# Sheet.net
KiCad netlist of a schematic drawn in Altium Designer
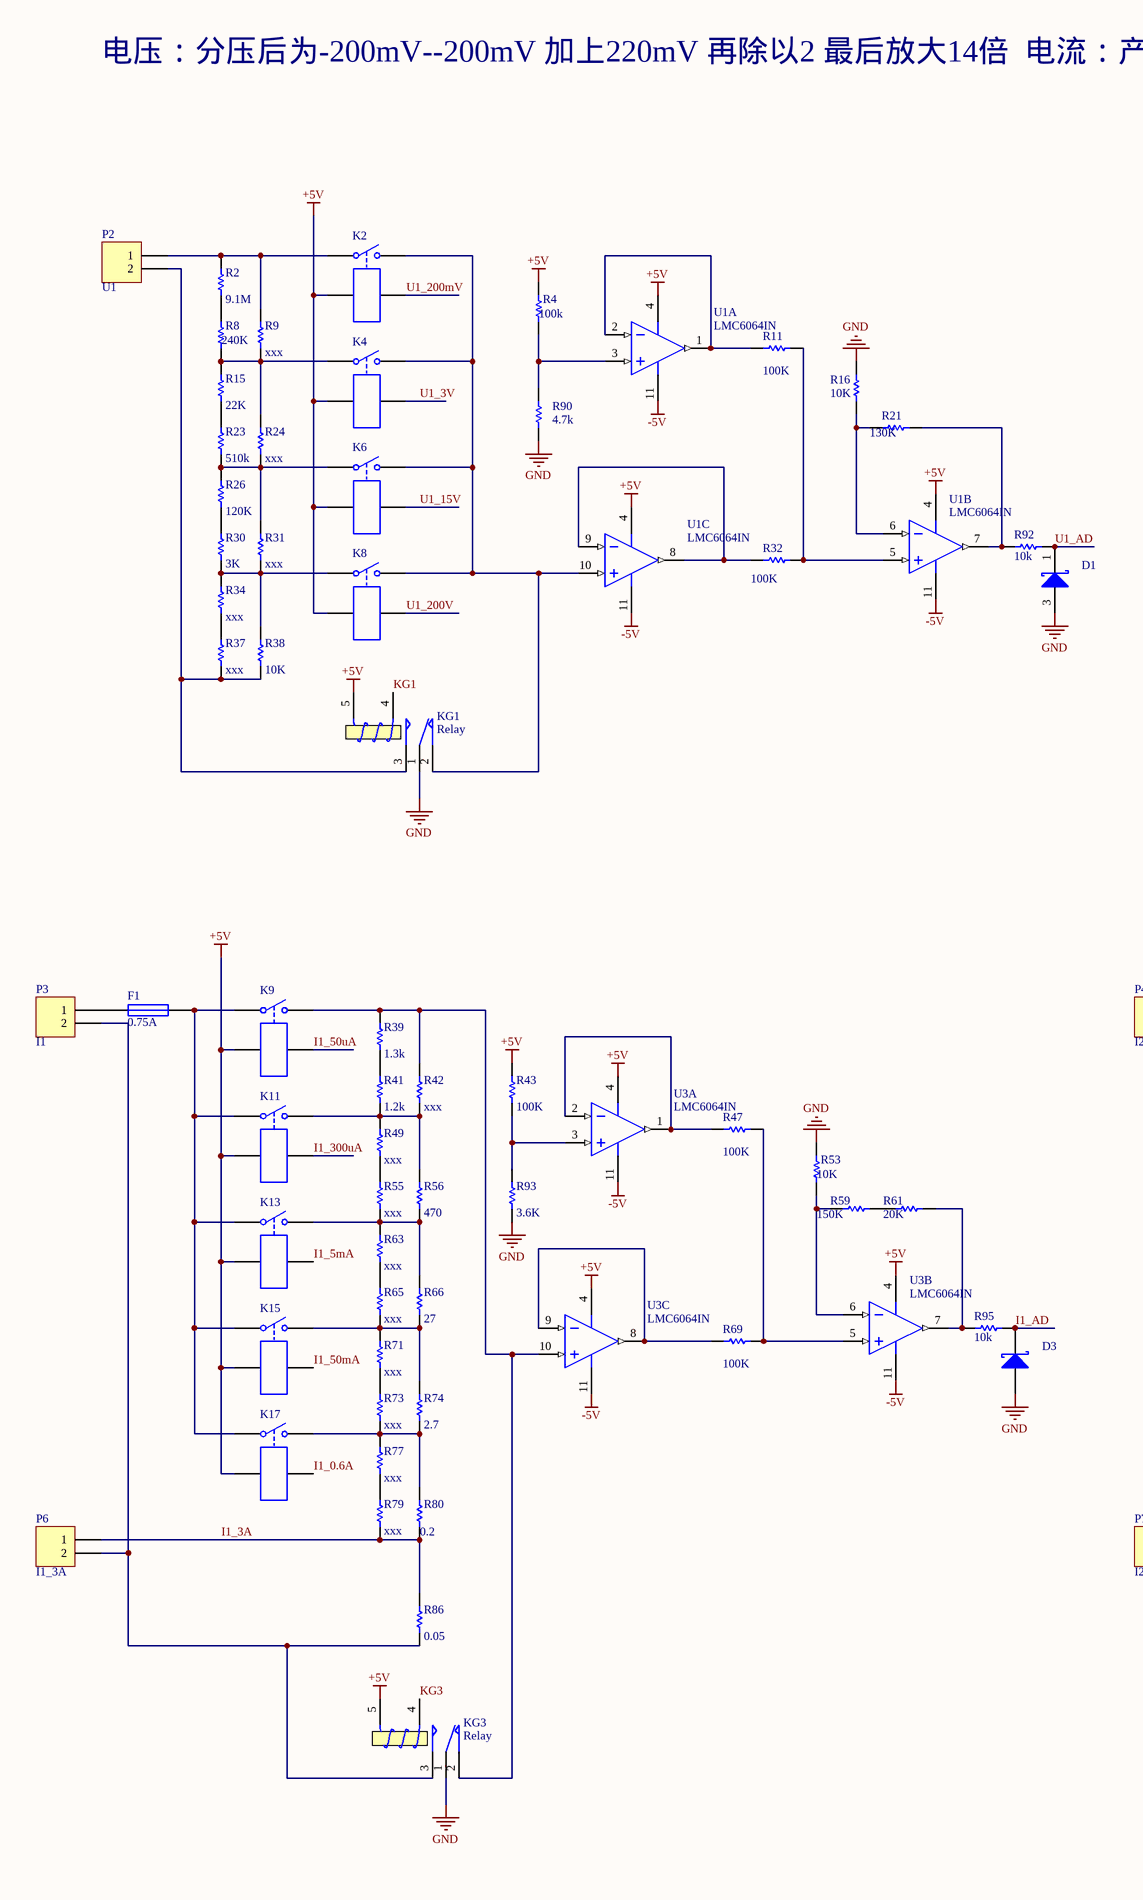
[diagram p0: Sheet.SchDoc, left]
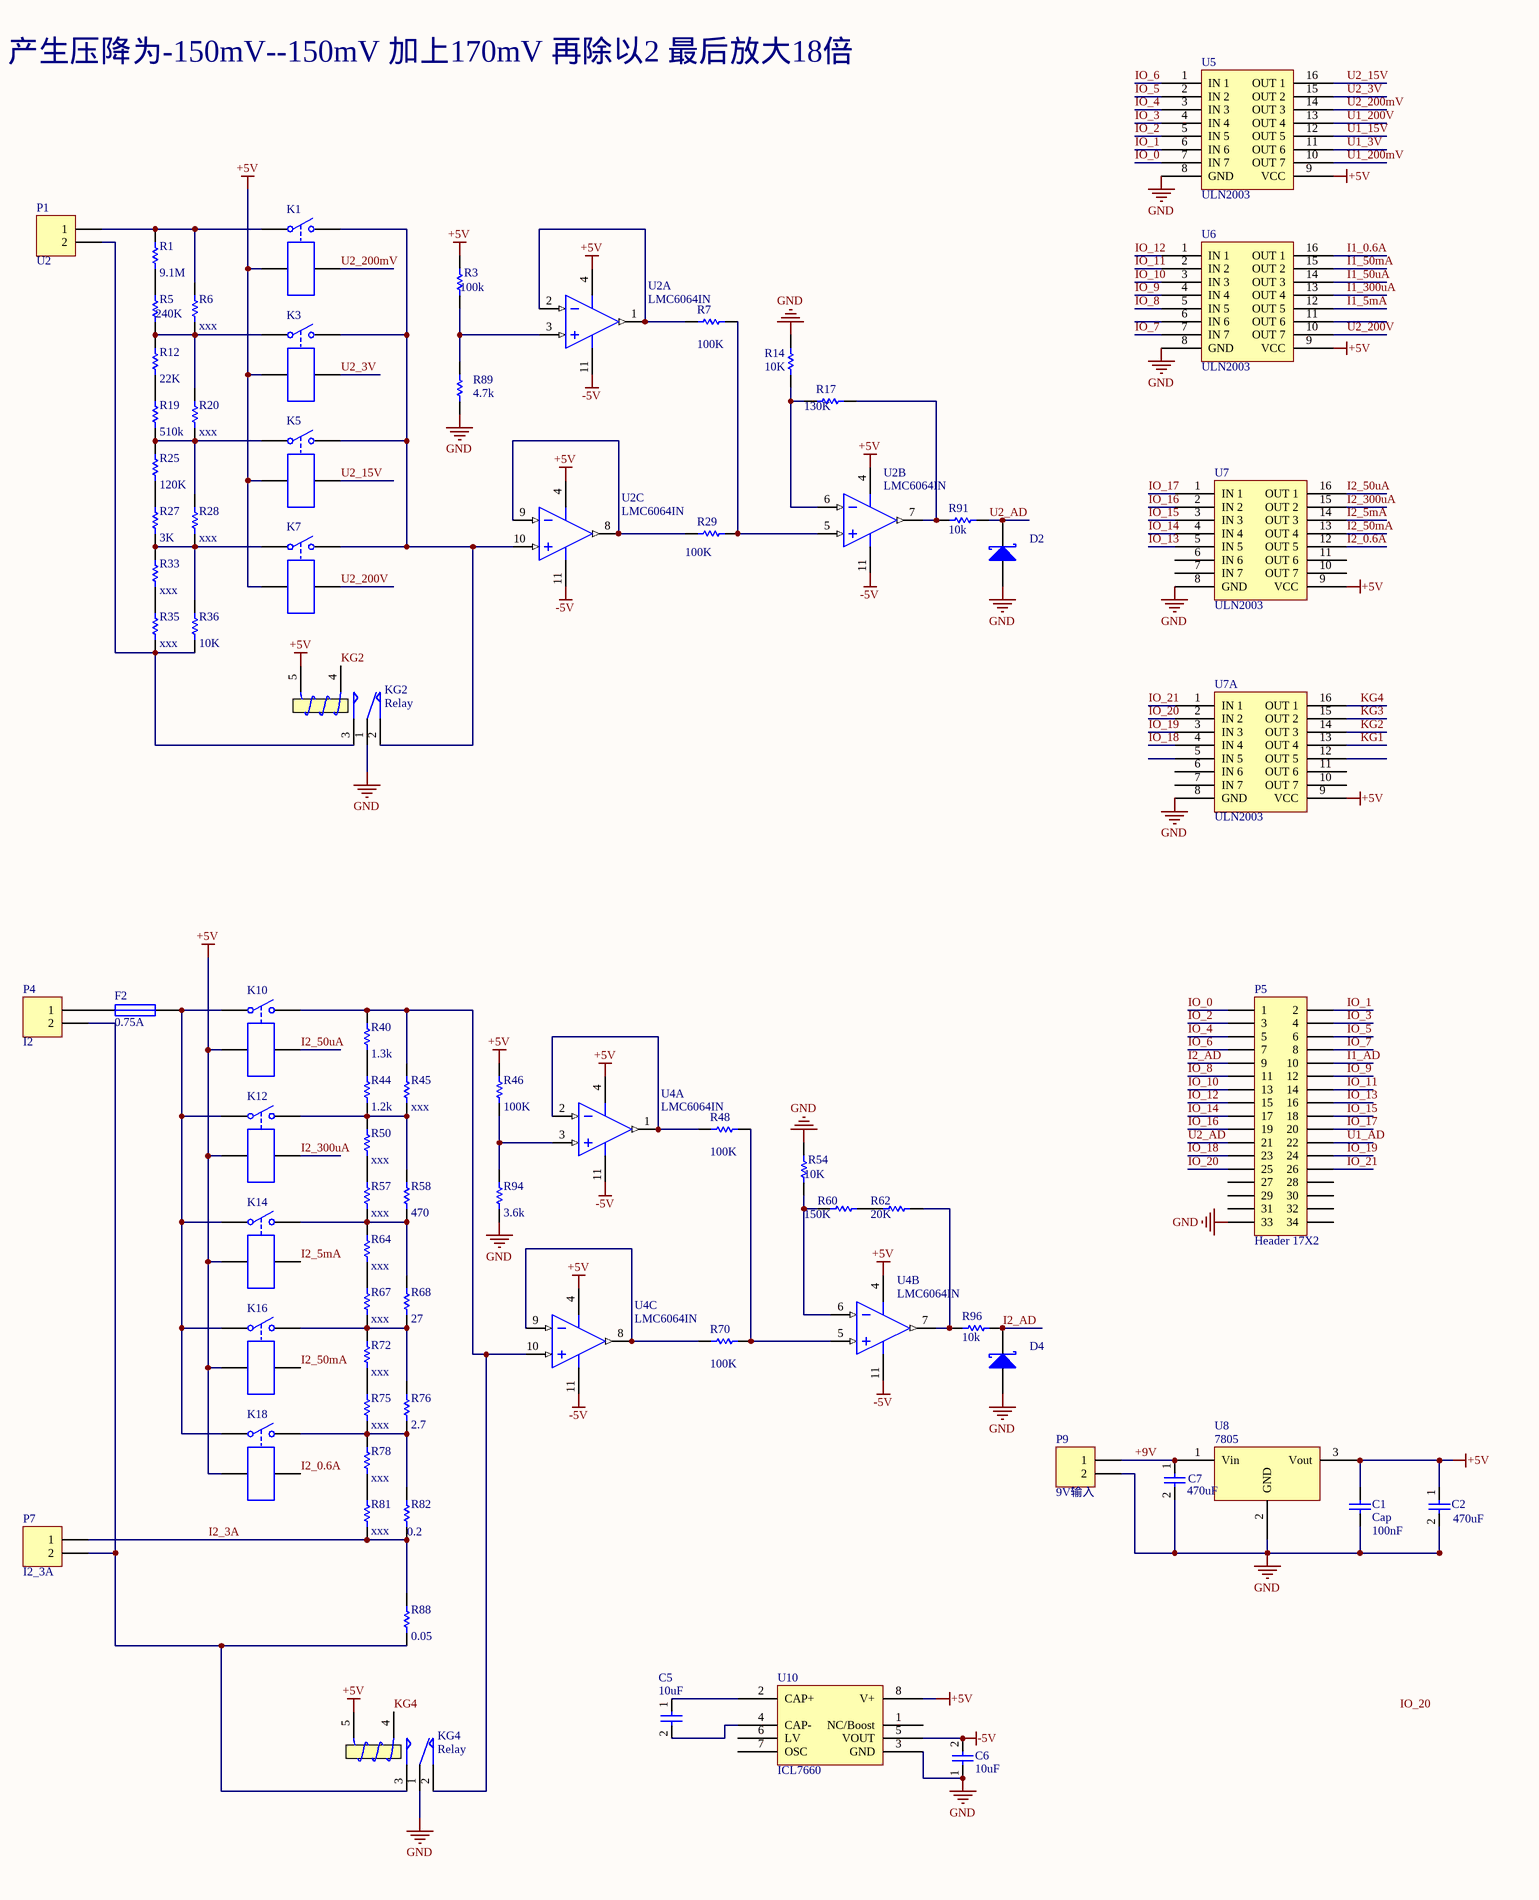
[diagram p1: Sheet.SchDoc, right]

(export (version "E")
  (design (tool "Eeschema 10.0.6"))
  (components
    (comp (ref "C1")
      (value "Cap")
      (footprint "0805")
      (description "Capacitor")
      (fields (field (name "ALTIUM_VALUE") "100nF") (field (name "PUBLISHER") "Altium Limited"))
      (libsource (lib "") (part "Cap_1"))
    )
    (comp (ref "C2")
      (value "470uF")
      (footprint "RB8mm_3.5mm")
      (description "Capacitor")
      (fields (field (name "Comment") "Cap") (field (name "PUBLISHER") "Altium Limited"))
      (libsource (lib "Miscellaneous Devices") (part "Cap"))
    )
    (comp (ref "C5")
      (value "10uF")
      (footprint "RB4.5mm_1.5mm")
      (description "Capacitor")
      (fields (field (name "Comment") "Cap") (field (name "PUBLISHER") "Altium Limited"))
      (libsource (lib "Miscellaneous Devices") (part "Cap"))
    )
    (comp (ref "C6")
      (value "10uF")
      (footprint "RB4.5mm_1.5mm")
      (description "Capacitor")
      (fields (field (name "Comment") "Cap") (field (name "PUBLISHER") "Altium Limited"))
      (libsource (lib "Miscellaneous Devices") (part "Cap"))
    )
    (comp (ref "C7")
      (value "470uF")
      (footprint "RB8mm_3.5mm")
      (description "Capacitor")
      (fields (field (name "Comment") "Cap") (field (name "PUBLISHER") "Altium Limited"))
      (libsource (lib "Miscellaneous Devices") (part "Cap"))
    )
    (comp (ref "D1")
      (value "~")
      (footprint "D1206")
      (description "Schottky Rectifier")
      (fields (field (name "PUBLISHER") "Altium Limited"))
      (libsource (lib "Miscellaneous Devices") (part "Diode 10TQ035"))
    )
    (comp (ref "D2")
      (value "~")
      (footprint "D1206")
      (description "Schottky Rectifier")
      (fields (field (name "PUBLISHER") "Altium Limited"))
      (libsource (lib "") (part "Diode 10TQ035_1"))
    )
    (comp (ref "D3")
      (value "~")
      (footprint "D1206")
      (description "Schottky Rectifier")
      (fields (field (name "PUBLISHER") "Altium Limited"))
      (libsource (lib "") (part "Diode 10TQ035_1"))
    )
    (comp (ref "D4")
      (value "~")
      (footprint "D1206")
      (description "Schottky Rectifier")
      (fields (field (name "PUBLISHER") "Altium Limited"))
      (libsource (lib "") (part "Diode 10TQ035_1"))
    )
    (comp (ref "F1")
      (value "0.75A")
      (footprint "1812")
      (description "Fuse")
      (fields (field (name "PUBLISHER") "Altium Limited"))
      (libsource (lib "Miscellaneous Devices") (part "Fuse 1"))
    )
    (comp (ref "F2")
      (value "0.75A")
      (footprint "1812")
      (description "Fuse")
      (fields (field (name "PUBLISHER") "Altium Limited"))
      (libsource (lib "Miscellaneous Devices") (part "Fuse 1"))
    )
    (comp (ref "K1")
      (value "Relay-SPST")
      (footprint "MyRelay")
      (description "Single-Pole Single-Throw Relay")
      (fields (field (name "PUBLISHER") "Altium Limited"))
      (libsource (lib "Miscellaneous Devices") (part "Relay-SPST"))
    )
    (comp (ref "K2")
      (value "Relay-SPST")
      (footprint "MyRelay")
      (description "Single-Pole Single-Throw Relay")
      (fields (field (name "PUBLISHER") "Altium Limited"))
      (libsource (lib "Miscellaneous Devices") (part "Relay-SPST"))
    )
    (comp (ref "K3")
      (value "Relay-SPST")
      (footprint "MyRelay")
      (description "Single-Pole Single-Throw Relay")
      (fields (field (name "PUBLISHER") "Altium Limited"))
      (libsource (lib "Miscellaneous Devices") (part "Relay-SPST"))
    )
    (comp (ref "K4")
      (value "Relay-SPST")
      (footprint "MyRelay")
      (description "Single-Pole Single-Throw Relay")
      (fields (field (name "PUBLISHER") "Altium Limited"))
      (libsource (lib "Miscellaneous Devices") (part "Relay-SPST"))
    )
    (comp (ref "K5")
      (value "Relay-SPST")
      (footprint "MyRelay")
      (description "Single-Pole Single-Throw Relay")
      (fields (field (name "PUBLISHER") "Altium Limited"))
      (libsource (lib "Miscellaneous Devices") (part "Relay-SPST"))
    )
    (comp (ref "K6")
      (value "Relay-SPST")
      (footprint "MyRelay")
      (description "Single-Pole Single-Throw Relay")
      (fields (field (name "PUBLISHER") "Altium Limited"))
      (libsource (lib "Miscellaneous Devices") (part "Relay-SPST"))
    )
    (comp (ref "K7")
      (value "Relay-SPST")
      (footprint "MyRelay")
      (description "Single-Pole Single-Throw Relay")
      (fields (field (name "PUBLISHER") "Altium Limited"))
      (libsource (lib "Miscellaneous Devices") (part "Relay-SPST"))
    )
    (comp (ref "K8")
      (value "Relay-SPST")
      (footprint "MyRelay")
      (description "Single-Pole Single-Throw Relay")
      (fields (field (name "PUBLISHER") "Altium Limited"))
      (libsource (lib "Miscellaneous Devices") (part "Relay-SPST"))
    )
    (comp (ref "K9")
      (value "Relay-SPST")
      (footprint "MyRelay")
      (description "Single-Pole Single-Throw Relay")
      (fields (field (name "PUBLISHER") "Altium Limited"))
      (libsource (lib "Miscellaneous Devices") (part "Relay-SPST"))
    )
    (comp (ref "K10")
      (value "Relay-SPST")
      (footprint "MyRelay")
      (description "Single-Pole Single-Throw Relay")
      (fields (field (name "PUBLISHER") "Altium Limited"))
      (libsource (lib "Miscellaneous Devices") (part "Relay-SPST"))
    )
    (comp (ref "K11")
      (value "Relay-SPST")
      (footprint "MyRelay")
      (description "Single-Pole Single-Throw Relay")
      (fields (field (name "PUBLISHER") "Altium Limited"))
      (libsource (lib "Miscellaneous Devices") (part "Relay-SPST"))
    )
    (comp (ref "K12")
      (value "Relay-SPST")
      (footprint "MyRelay")
      (description "Single-Pole Single-Throw Relay")
      (fields (field (name "PUBLISHER") "Altium Limited"))
      (libsource (lib "Miscellaneous Devices") (part "Relay-SPST"))
    )
    (comp (ref "K13")
      (value "Relay-SPST")
      (footprint "MyRelay")
      (description "Single-Pole Single-Throw Relay")
      (fields (field (name "PUBLISHER") "Altium Limited"))
      (libsource (lib "Miscellaneous Devices") (part "Relay-SPST"))
    )
    (comp (ref "K14")
      (value "Relay-SPST")
      (footprint "MyRelay")
      (description "Single-Pole Single-Throw Relay")
      (fields (field (name "PUBLISHER") "Altium Limited"))
      (libsource (lib "Miscellaneous Devices") (part "Relay-SPST"))
    )
    (comp (ref "K15")
      (value "Relay-SPST")
      (footprint "MyRelay")
      (description "Single-Pole Single-Throw Relay")
      (fields (field (name "PUBLISHER") "Altium Limited"))
      (libsource (lib "Miscellaneous Devices") (part "Relay-SPST"))
    )
    (comp (ref "K16")
      (value "Relay-SPST")
      (footprint "MyRelay")
      (description "Single-Pole Single-Throw Relay")
      (fields (field (name "PUBLISHER") "Altium Limited"))
      (libsource (lib "Miscellaneous Devices") (part "Relay-SPST"))
    )
    (comp (ref "K17")
      (value "Relay-SPST")
      (footprint "MyRelay")
      (description "Single-Pole Single-Throw Relay")
      (fields (field (name "PUBLISHER") "Altium Limited"))
      (libsource (lib "Miscellaneous Devices") (part "Relay-SPST"))
    )
    (comp (ref "K18")
      (value "Relay-SPST")
      (footprint "MyRelay")
      (description "Single-Pole Single-Throw Relay")
      (fields (field (name "PUBLISHER") "Altium Limited"))
      (libsource (lib "Miscellaneous Devices") (part "Relay-SPST"))
    )
    (comp (ref "KG1")
      (value "Relay")
      (footprint "RELAY_HK4101F")
      (description "SPDT Relay")
      (fields (field (name "PUBLISHER") "Altium Limited"))
      (libsource (lib "Miscellaneous Devices") (part "Relay"))
    )
    (comp (ref "KG2")
      (value "Relay")
      (footprint "RELAY_HK4101F")
      (description "SPDT Relay")
      (fields (field (name "PUBLISHER") "Altium Limited"))
      (libsource (lib "Miscellaneous Devices") (part "Relay"))
    )
    (comp (ref "KG3")
      (value "Relay")
      (footprint "RELAY_HK4101F")
      (description "SPDT Relay")
      (fields (field (name "PUBLISHER") "Altium Limited"))
      (libsource (lib "Miscellaneous Devices") (part "Relay"))
    )
    (comp (ref "KG4")
      (value "Relay")
      (footprint "RELAY_HK4101F")
      (description "SPDT Relay")
      (fields (field (name "PUBLISHER") "Altium Limited"))
      (libsource (lib "Miscellaneous Devices") (part "Relay"))
    )
    (comp (ref "P1")
      (value "U2")
      (footprint "MyCon2")
      (description "Header, 2-Pin")
      (fields (field (name "PUBLISHER") "Altium Limited"))
      (libsource (lib "Miscellaneous Connectors") (part "Header 2"))
    )
    (comp (ref "P2")
      (value "U1")
      (footprint "MyCon2")
      (description "Header, 2-Pin")
      (fields (field (name "PUBLISHER") "Altium Limited"))
      (libsource (lib "Miscellaneous Connectors") (part "Header 2"))
    )
    (comp (ref "P3")
      (value "I1")
      (footprint "MyCon2")
      (description "Header, 2-Pin")
      (fields (field (name "PUBLISHER") "Altium Limited"))
      (libsource (lib "Miscellaneous Connectors") (part "Header 2"))
    )
    (comp (ref "P4")
      (value "I2")
      (footprint "MyCon2")
      (description "Header, 2-Pin")
      (fields (field (name "PUBLISHER") "Altium Limited"))
      (libsource (lib "Miscellaneous Connectors") (part "Header 2"))
    )
    (comp (ref "P5")
      (value "Header 17X2")
      (footprint "IDC34S")
      (description "Header, 17-Pin, Dual row")
      (fields (field (name "PUBLISHER") "Altium Limited"))
      (libsource (lib "Miscellaneous Connectors") (part "Header 17X2"))
    )
    (comp (ref "P6")
      (value "I1_3A")
      (footprint "MyCon2")
      (description "Header, 2-Pin")
      (fields (field (name "PUBLISHER") "Altium Limited"))
      (libsource (lib "Miscellaneous Connectors") (part "Header 2"))
    )
    (comp (ref "P7")
      (value "I2_3A")
      (footprint "MyCon2")
      (description "Header, 2-Pin")
      (fields (field (name "PUBLISHER") "Altium Limited"))
      (libsource (lib "Miscellaneous Connectors") (part "Header 2"))
    )
    (comp (ref "P9")
      (value "9V输入")
      (footprint "XH2.0-2p")
      (description "Header, 2-Pin")
      (fields (field (name "PUBLISHER") "Altium Limited"))
      (libsource (lib "Miscellaneous Connectors") (part "Header 2"))
    )
    (comp (ref "R1")
      (value "9.1M")
      (footprint "0603R")
      (description "Resistor")
      (fields (field (name "Comment") "Res1") (field (name "PUBLISHER") "Altium Limited"))
      (libsource (lib "Miscellaneous Devices") (part "Res1"))
    )
    (comp (ref "R2")
      (value "9.1M")
      (footprint "0603R")
      (description "Resistor")
      (fields (field (name "Comment") "Res1") (field (name "PUBLISHER") "Altium Limited"))
      (libsource (lib "Miscellaneous Devices") (part "Res1"))
    )
    (comp (ref "R3")
      (value "100k")
      (footprint "0603R")
      (description "Resistor")
      (fields (field (name "Comment") "Res1") (field (name "PUBLISHER") "Altium Limited"))
      (libsource (lib "Miscellaneous Devices") (part "Res1"))
    )
    (comp (ref "R4")
      (value "100k")
      (footprint "0603R")
      (description "Resistor")
      (fields (field (name "Comment") "Res1") (field (name "PUBLISHER") "Altium Limited"))
      (libsource (lib "Miscellaneous Devices") (part "Res1"))
    )
    (comp (ref "R5")
      (value "240K")
      (footprint "0603R")
      (description "Resistor")
      (fields (field (name "Comment") "Res1") (field (name "PUBLISHER") "Altium Limited"))
      (libsource (lib "Miscellaneous Devices") (part "Res1"))
    )
    (comp (ref "R6")
      (value "xxx")
      (footprint "0603R")
      (description "Resistor")
      (fields (field (name "Comment") "Res1") (field (name "PUBLISHER") "Altium Limited"))
      (libsource (lib "Miscellaneous Devices") (part "Res1"))
    )
    (comp (ref "R7")
      (value "100K")
      (footprint "0603R")
      (description "Resistor")
      (fields (field (name "Comment") "Res1") (field (name "PUBLISHER") "Altium Limited"))
      (libsource (lib "Miscellaneous Devices") (part "Res1"))
    )
    (comp (ref "R8")
      (value "240K")
      (footprint "0603R")
      (description "Resistor")
      (fields (field (name "Comment") "Res1") (field (name "PUBLISHER") "Altium Limited"))
      (libsource (lib "Miscellaneous Devices") (part "Res1"))
    )
    (comp (ref "R9")
      (value "xxx")
      (footprint "0603R")
      (description "Resistor")
      (fields (field (name "Comment") "Res1") (field (name "PUBLISHER") "Altium Limited"))
      (libsource (lib "Miscellaneous Devices") (part "Res1"))
    )
    (comp (ref "R11")
      (value "100K")
      (footprint "0603R")
      (description "Resistor")
      (fields (field (name "Comment") "Res1") (field (name "PUBLISHER") "Altium Limited"))
      (libsource (lib "Miscellaneous Devices") (part "Res1"))
    )
    (comp (ref "R12")
      (value "22K")
      (footprint "0603R")
      (description "Resistor")
      (fields (field (name "Comment") "Res1") (field (name "PUBLISHER") "Altium Limited"))
      (libsource (lib "Miscellaneous Devices") (part "Res1"))
    )
    (comp (ref "R14")
      (value "10K")
      (footprint "0603R")
      (description "Resistor")
      (fields (field (name "Comment") "Res1") (field (name "PUBLISHER") "Altium Limited"))
      (libsource (lib "Miscellaneous Devices") (part "Res1"))
    )
    (comp (ref "R15")
      (value "22K")
      (footprint "0603R")
      (description "Resistor")
      (fields (field (name "Comment") "Res1") (field (name "PUBLISHER") "Altium Limited"))
      (libsource (lib "Miscellaneous Devices") (part "Res1"))
    )
    (comp (ref "R16")
      (value "10K")
      (footprint "0603R")
      (description "Resistor")
      (fields (field (name "Comment") "Res1") (field (name "PUBLISHER") "Altium Limited"))
      (libsource (lib "Miscellaneous Devices") (part "Res1"))
    )
    (comp (ref "R17")
      (value "130K")
      (footprint "0603R")
      (description "Resistor")
      (fields (field (name "Comment") "Res1") (field (name "PUBLISHER") "Altium Limited"))
      (libsource (lib "Miscellaneous Devices") (part "Res1"))
    )
    (comp (ref "R19")
      (value "510k")
      (footprint "0603R")
      (description "Resistor")
      (fields (field (name "Comment") "Res1") (field (name "PUBLISHER") "Altium Limited"))
      (libsource (lib "Miscellaneous Devices") (part "Res1"))
    )
    (comp (ref "R20")
      (value "xxx")
      (footprint "0603R")
      (description "Resistor")
      (fields (field (name "Comment") "Res1") (field (name "PUBLISHER") "Altium Limited"))
      (libsource (lib "Miscellaneous Devices") (part "Res1"))
    )
    (comp (ref "R21")
      (value "130K")
      (footprint "0603R")
      (description "Resistor")
      (fields (field (name "Comment") "Res1") (field (name "PUBLISHER") "Altium Limited"))
      (libsource (lib "Miscellaneous Devices") (part "Res1"))
    )
    (comp (ref "R23")
      (value "510k")
      (footprint "0603R")
      (description "Resistor")
      (fields (field (name "Comment") "Res1") (field (name "PUBLISHER") "Altium Limited"))
      (libsource (lib "Miscellaneous Devices") (part "Res1"))
    )
    (comp (ref "R24")
      (value "xxx")
      (footprint "0603R")
      (description "Resistor")
      (fields (field (name "Comment") "Res1") (field (name "PUBLISHER") "Altium Limited"))
      (libsource (lib "Miscellaneous Devices") (part "Res1"))
    )
    (comp (ref "R25")
      (value "120K")
      (footprint "0603R")
      (description "Resistor")
      (fields (field (name "Comment") "Res1") (field (name "PUBLISHER") "Altium Limited"))
      (libsource (lib "Miscellaneous Devices") (part "Res1"))
    )
    (comp (ref "R26")
      (value "120K")
      (footprint "0603R")
      (description "Resistor")
      (fields (field (name "Comment") "Res1") (field (name "PUBLISHER") "Altium Limited"))
      (libsource (lib "Miscellaneous Devices") (part "Res1"))
    )
    (comp (ref "R27")
      (value "3K")
      (footprint "0603R")
      (description "Resistor")
      (fields (field (name "Comment") "Res1") (field (name "PUBLISHER") "Altium Limited"))
      (libsource (lib "Miscellaneous Devices") (part "Res1"))
    )
    (comp (ref "R28")
      (value "xxx")
      (footprint "0603R")
      (description "Resistor")
      (fields (field (name "Comment") "Res1") (field (name "PUBLISHER") "Altium Limited"))
      (libsource (lib "Miscellaneous Devices") (part "Res1"))
    )
    (comp (ref "R29")
      (value "100K")
      (footprint "0603R")
      (description "Resistor")
      (fields (field (name "Comment") "Res1") (field (name "PUBLISHER") "Altium Limited"))
      (libsource (lib "Miscellaneous Devices") (part "Res1"))
    )
    (comp (ref "R30")
      (value "3K")
      (footprint "0603R")
      (description "Resistor")
      (fields (field (name "Comment") "Res1") (field (name "PUBLISHER") "Altium Limited"))
      (libsource (lib "Miscellaneous Devices") (part "Res1"))
    )
    (comp (ref "R31")
      (value "xxx")
      (footprint "0603R")
      (description "Resistor")
      (fields (field (name "Comment") "Res1") (field (name "PUBLISHER") "Altium Limited"))
      (libsource (lib "Miscellaneous Devices") (part "Res1"))
    )
    (comp (ref "R32")
      (value "100K")
      (footprint "0603R")
      (description "Resistor")
      (fields (field (name "Comment") "Res1") (field (name "PUBLISHER") "Altium Limited"))
      (libsource (lib "Miscellaneous Devices") (part "Res1"))
    )
    (comp (ref "R33")
      (value "xxx")
      (footprint "0603R")
      (description "Resistor")
      (fields (field (name "Comment") "Res1") (field (name "PUBLISHER") "Altium Limited"))
      (libsource (lib "Miscellaneous Devices") (part "Res1"))
    )
    (comp (ref "R34")
      (value "xxx")
      (footprint "0603R")
      (description "Resistor")
      (fields (field (name "Comment") "Res1") (field (name "PUBLISHER") "Altium Limited"))
      (libsource (lib "Miscellaneous Devices") (part "Res1"))
    )
    (comp (ref "R35")
      (value "xxx")
      (footprint "0603R")
      (description "Resistor")
      (fields (field (name "Comment") "Res1") (field (name "PUBLISHER") "Altium Limited"))
      (libsource (lib "Miscellaneous Devices") (part "Res1"))
    )
    (comp (ref "R36")
      (value "10K")
      (footprint "0603R")
      (description "Resistor")
      (fields (field (name "Comment") "Res1") (field (name "PUBLISHER") "Altium Limited"))
      (libsource (lib "Miscellaneous Devices") (part "Res1"))
    )
    (comp (ref "R37")
      (value "xxx")
      (footprint "0603R")
      (description "Resistor")
      (fields (field (name "Comment") "Res1") (field (name "PUBLISHER") "Altium Limited"))
      (libsource (lib "Miscellaneous Devices") (part "Res1"))
    )
    (comp (ref "R38")
      (value "10K")
      (footprint "0603R")
      (description "Resistor")
      (fields (field (name "Comment") "Res1") (field (name "PUBLISHER") "Altium Limited"))
      (libsource (lib "Miscellaneous Devices") (part "Res1"))
    )
    (comp (ref "R39")
      (value "1.3k")
      (footprint "1206")
      (description "Resistor")
      (fields (field (name "Comment") "Res1") (field (name "PUBLISHER") "Altium Limited"))
      (libsource (lib "Miscellaneous Devices") (part "Res1"))
    )
    (comp (ref "R40")
      (value "1.3k")
      (footprint "1206")
      (description "Resistor")
      (fields (field (name "Comment") "Res1") (field (name "PUBLISHER") "Altium Limited"))
      (libsource (lib "Miscellaneous Devices") (part "Res1"))
    )
    (comp (ref "R41")
      (value "1.2k")
      (footprint "1206")
      (description "Resistor")
      (fields (field (name "Comment") "Res1") (field (name "PUBLISHER") "Altium Limited"))
      (libsource (lib "Miscellaneous Devices") (part "Res1"))
    )
    (comp (ref "R42")
      (value "xxx")
      (footprint "1206")
      (description "Resistor")
      (fields (field (name "Comment") "Res1") (field (name "PUBLISHER") "Altium Limited"))
      (libsource (lib "Miscellaneous Devices") (part "Res1"))
    )
    (comp (ref "R43")
      (value "100K")
      (footprint "0603R")
      (description "Resistor")
      (fields (field (name "Comment") "Res1") (field (name "PUBLISHER") "Altium Limited"))
      (libsource (lib "Miscellaneous Devices") (part "Res1"))
    )
    (comp (ref "R44")
      (value "1.2k")
      (footprint "1206")
      (description "Resistor")
      (fields (field (name "Comment") "Res1") (field (name "PUBLISHER") "Altium Limited"))
      (libsource (lib "Miscellaneous Devices") (part "Res1"))
    )
    (comp (ref "R45")
      (value "xxx")
      (footprint "1206")
      (description "Resistor")
      (fields (field (name "Comment") "Res1") (field (name "PUBLISHER") "Altium Limited"))
      (libsource (lib "Miscellaneous Devices") (part "Res1"))
    )
    (comp (ref "R46")
      (value "100K")
      (footprint "0603R")
      (description "Resistor")
      (fields (field (name "Comment") "Res1") (field (name "PUBLISHER") "Altium Limited"))
      (libsource (lib "Miscellaneous Devices") (part "Res1"))
    )
    (comp (ref "R47")
      (value "100K")
      (footprint "0603R")
      (description "Resistor")
      (fields (field (name "Comment") "Res1") (field (name "PUBLISHER") "Altium Limited"))
      (libsource (lib "Miscellaneous Devices") (part "Res1"))
    )
    (comp (ref "R48")
      (value "100K")
      (footprint "0603R")
      (description "Resistor")
      (fields (field (name "Comment") "Res1") (field (name "PUBLISHER") "Altium Limited"))
      (libsource (lib "Miscellaneous Devices") (part "Res1"))
    )
    (comp (ref "R49")
      (value "xxx")
      (footprint "1206")
      (description "Resistor")
      (fields (field (name "Comment") "Res1") (field (name "PUBLISHER") "Altium Limited"))
      (libsource (lib "Miscellaneous Devices") (part "Res1"))
    )
    (comp (ref "R50")
      (value "xxx")
      (footprint "1206")
      (description "Resistor")
      (fields (field (name "Comment") "Res1") (field (name "PUBLISHER") "Altium Limited"))
      (libsource (lib "Miscellaneous Devices") (part "Res1"))
    )
    (comp (ref "R53")
      (value "10K")
      (footprint "0603R")
      (description "Resistor")
      (fields (field (name "Comment") "Res1") (field (name "PUBLISHER") "Altium Limited"))
      (libsource (lib "Miscellaneous Devices") (part "Res1"))
    )
    (comp (ref "R54")
      (value "10K")
      (footprint "0603R")
      (description "Resistor")
      (fields (field (name "Comment") "Res1") (field (name "PUBLISHER") "Altium Limited"))
      (libsource (lib "Miscellaneous Devices") (part "Res1"))
    )
    (comp (ref "R55")
      (value "xxx")
      (footprint "1206")
      (description "Resistor")
      (fields (field (name "Comment") "Res1") (field (name "PUBLISHER") "Altium Limited"))
      (libsource (lib "Miscellaneous Devices") (part "Res1"))
    )
    (comp (ref "R56")
      (value "470")
      (footprint "1206")
      (description "Resistor")
      (fields (field (name "Comment") "Res1") (field (name "PUBLISHER") "Altium Limited"))
      (libsource (lib "Miscellaneous Devices") (part "Res1"))
    )
    (comp (ref "R57")
      (value "xxx")
      (footprint "1206")
      (description "Resistor")
      (fields (field (name "Comment") "Res1") (field (name "PUBLISHER") "Altium Limited"))
      (libsource (lib "Miscellaneous Devices") (part "Res1"))
    )
    (comp (ref "R58")
      (value "470")
      (footprint "1206")
      (description "Resistor")
      (fields (field (name "Comment") "Res1") (field (name "PUBLISHER") "Altium Limited"))
      (libsource (lib "Miscellaneous Devices") (part "Res1"))
    )
    (comp (ref "R59")
      (value "150K")
      (footprint "0603R")
      (description "Resistor")
      (fields (field (name "Comment") "Res1") (field (name "PUBLISHER") "Altium Limited"))
      (libsource (lib "Miscellaneous Devices") (part "Res1"))
    )
    (comp (ref "R60")
      (value "150K")
      (footprint "0603R")
      (description "Resistor")
      (fields (field (name "Comment") "Res1") (field (name "PUBLISHER") "Altium Limited"))
      (libsource (lib "Miscellaneous Devices") (part "Res1"))
    )
    (comp (ref "R61")
      (value "20K")
      (footprint "0603R")
      (description "Resistor")
      (fields (field (name "Comment") "Res1") (field (name "PUBLISHER") "Altium Limited"))
      (libsource (lib "Miscellaneous Devices") (part "Res1"))
    )
    (comp (ref "R62")
      (value "20K")
      (footprint "0603R")
      (description "Resistor")
      (fields (field (name "Comment") "Res1") (field (name "PUBLISHER") "Altium Limited"))
      (libsource (lib "Miscellaneous Devices") (part "Res1"))
    )
    (comp (ref "R63")
      (value "xxx")
      (footprint "1206")
      (description "Resistor")
      (fields (field (name "Comment") "Res1") (field (name "PUBLISHER") "Altium Limited"))
      (libsource (lib "Miscellaneous Devices") (part "Res1"))
    )
    (comp (ref "R64")
      (value "xxx")
      (footprint "1206")
      (description "Resistor")
      (fields (field (name "Comment") "Res1") (field (name "PUBLISHER") "Altium Limited"))
      (libsource (lib "Miscellaneous Devices") (part "Res1"))
    )
    (comp (ref "R65")
      (value "xxx")
      (footprint "1206")
      (description "Resistor")
      (fields (field (name "Comment") "Res1") (field (name "PUBLISHER") "Altium Limited"))
      (libsource (lib "Miscellaneous Devices") (part "Res1"))
    )
    (comp (ref "R66")
      (value "27")
      (footprint "1206")
      (description "Resistor")
      (fields (field (name "Comment") "Res1") (field (name "PUBLISHER") "Altium Limited"))
      (libsource (lib "Miscellaneous Devices") (part "Res1"))
    )
    (comp (ref "R67")
      (value "xxx")
      (footprint "1206")
      (description "Resistor")
      (fields (field (name "Comment") "Res1") (field (name "PUBLISHER") "Altium Limited"))
      (libsource (lib "Miscellaneous Devices") (part "Res1"))
    )
    (comp (ref "R68")
      (value "27")
      (footprint "1206")
      (description "Resistor")
      (fields (field (name "Comment") "Res1") (field (name "PUBLISHER") "Altium Limited"))
      (libsource (lib "Miscellaneous Devices") (part "Res1"))
    )
    (comp (ref "R69")
      (value "100K")
      (footprint "0603R")
      (description "Resistor")
      (fields (field (name "Comment") "Res1") (field (name "PUBLISHER") "Altium Limited"))
      (libsource (lib "Miscellaneous Devices") (part "Res1"))
    )
    (comp (ref "R70")
      (value "100K")
      (footprint "0603R")
      (description "Resistor")
      (fields (field (name "Comment") "Res1") (field (name "PUBLISHER") "Altium Limited"))
      (libsource (lib "Miscellaneous Devices") (part "Res1"))
    )
    (comp (ref "R71")
      (value "xxx")
      (footprint "1206")
      (description "Resistor")
      (fields (field (name "Comment") "Res1") (field (name "PUBLISHER") "Altium Limited"))
      (libsource (lib "Miscellaneous Devices") (part "Res1"))
    )
    (comp (ref "R72")
      (value "xxx")
      (footprint "1206")
      (description "Resistor")
      (fields (field (name "Comment") "Res1") (field (name "PUBLISHER") "Altium Limited"))
      (libsource (lib "Miscellaneous Devices") (part "Res1"))
    )
    (comp (ref "R73")
      (value "xxx")
      (footprint "1206")
      (description "Resistor")
      (fields (field (name "Comment") "Res1") (field (name "PUBLISHER") "Altium Limited"))
      (libsource (lib "Miscellaneous Devices") (part "Res1"))
    )
    (comp (ref "R74")
      (value "2.7")
      (footprint "1206")
      (description "Resistor")
      (fields (field (name "Comment") "Res1") (field (name "PUBLISHER") "Altium Limited"))
      (libsource (lib "Miscellaneous Devices") (part "Res1"))
    )
    (comp (ref "R75")
      (value "xxx")
      (footprint "1206")
      (description "Resistor")
      (fields (field (name "Comment") "Res1") (field (name "PUBLISHER") "Altium Limited"))
      (libsource (lib "Miscellaneous Devices") (part "Res1"))
    )
    (comp (ref "R76")
      (value "2.7")
      (footprint "1206")
      (description "Resistor")
      (fields (field (name "Comment") "Res1") (field (name "PUBLISHER") "Altium Limited"))
      (libsource (lib "Miscellaneous Devices") (part "Res1"))
    )
    (comp (ref "R77")
      (value "xxx")
      (footprint "1206")
      (description "Resistor")
      (fields (field (name "Comment") "Res1") (field (name "PUBLISHER") "Altium Limited"))
      (libsource (lib "Miscellaneous Devices") (part "Res1"))
    )
    (comp (ref "R78")
      (value "xxx")
      (footprint "1206")
      (description "Resistor")
      (fields (field (name "Comment") "Res1") (field (name "PUBLISHER") "Altium Limited"))
      (libsource (lib "Miscellaneous Devices") (part "Res1"))
    )
    (comp (ref "R79")
      (value "xxx")
      (footprint "1206")
      (description "Resistor")
      (fields (field (name "Comment") "Res1") (field (name "PUBLISHER") "Altium Limited"))
      (libsource (lib "Miscellaneous Devices") (part "Res1"))
    )
    (comp (ref "R80")
      (value "0.2")
      (footprint "1206")
      (description "Resistor")
      (fields (field (name "Comment") "Res1") (field (name "PUBLISHER") "Altium Limited"))
      (libsource (lib "Miscellaneous Devices") (part "Res1"))
    )
    (comp (ref "R81")
      (value "xxx")
      (footprint "1206")
      (description "Resistor")
      (fields (field (name "Comment") "Res1") (field (name "PUBLISHER") "Altium Limited"))
      (libsource (lib "Miscellaneous Devices") (part "Res1"))
    )
    (comp (ref "R82")
      (value "0.2")
      (footprint "1206")
      (description "Resistor")
      (fields (field (name "Comment") "Res1") (field (name "PUBLISHER") "Altium Limited"))
      (libsource (lib "Miscellaneous Devices") (part "Res1"))
    )
    (comp (ref "R86")
      (value "0.05")
      (footprint "MY2512")
      (description "Resistor")
      (fields (field (name "Comment") "Res1") (field (name "PUBLISHER") "Altium Limited"))
      (libsource (lib "Miscellaneous Devices") (part "Res1"))
    )
    (comp (ref "R88")
      (value "0.05")
      (footprint "MY2512")
      (description "Resistor")
      (fields (field (name "Comment") "Res1") (field (name "PUBLISHER") "Altium Limited"))
      (libsource (lib "Miscellaneous Devices") (part "Res1"))
    )
    (comp (ref "R89")
      (value "4.7k")
      (footprint "0603R")
      (description "Resistor")
      (fields (field (name "Comment") "Res1") (field (name "PUBLISHER") "Altium Limited"))
      (libsource (lib "Miscellaneous Devices") (part "Res1"))
    )
    (comp (ref "R90")
      (value "4.7k")
      (footprint "0603R")
      (description "Resistor")
      (fields (field (name "Comment") "Res1") (field (name "PUBLISHER") "Altium Limited"))
      (libsource (lib "Miscellaneous Devices") (part "Res1"))
    )
    (comp (ref "R91")
      (value "10k")
      (footprint "0603R")
      (description "Resistor")
      (fields (field (name "Comment") "Res1") (field (name "PUBLISHER") "Altium Limited"))
      (libsource (lib "Miscellaneous Devices") (part "Res1"))
    )
    (comp (ref "R92")
      (value "10k")
      (footprint "0603R")
      (description "Resistor")
      (fields (field (name "Comment") "Res1") (field (name "PUBLISHER") "Altium Limited"))
      (libsource (lib "Miscellaneous Devices") (part "Res1"))
    )
    (comp (ref "R93")
      (value "3.6K")
      (footprint "0603R")
      (description "Resistor")
      (fields (field (name "Comment") "Res1") (field (name "PUBLISHER") "Altium Limited"))
      (libsource (lib "Miscellaneous Devices") (part "Res1"))
    )
    (comp (ref "R94")
      (value "3.6k")
      (footprint "0603R")
      (description "Resistor")
      (fields (field (name "Comment") "Res1") (field (name "PUBLISHER") "Altium Limited"))
      (libsource (lib "Miscellaneous Devices") (part "Res1"))
    )
    (comp (ref "R95")
      (value "10k")
      (footprint "0603R")
      (description "Resistor")
      (fields (field (name "Comment") "Res1") (field (name "PUBLISHER") "Altium Limited"))
      (libsource (lib "Miscellaneous Devices") (part "Res1"))
    )
    (comp (ref "R96")
      (value "10k")
      (footprint "0603R")
      (description "Resistor")
      (fields (field (name "Comment") "Res1") (field (name "PUBLISHER") "Altium Limited"))
      (libsource (lib "Miscellaneous Devices") (part "Res1"))
    )
    (comp (ref "U1")
      (value "LMC6064IN")
      (footprint "N14A")
      (description "Precision CMOS Quad Micropower Operational Amplifier")
      (fields
        (field (name "MANUFACTURER") "National Semiconductor")
        (field (name "DIGIKEYPARTNUMBER") "LMC6064IN-ND")
        (field (name "PUBLISHER") "Altium Limited")
      )
      (libsource (lib "NSC Amplifier") (part "LMC6064IN"))
    )
    (comp (ref "U2")
      (value "LMC6064IN")
      (footprint "N14A")
      (description "Precision CMOS Quad Micropower Operational Amplifier")
      (fields
        (field (name "MANUFACTURER") "National Semiconductor")
        (field (name "DIGIKEYPARTNUMBER") "LMC6064IN-ND")
        (field (name "PUBLISHER") "Altium Limited")
      )
      (libsource (lib "NSC Amplifier") (part "LMC6064IN"))
    )
    (comp (ref "U3")
      (value "LMC6064IN")
      (footprint "N14A")
      (description "Precision CMOS Quad Micropower Operational Amplifier")
      (fields
        (field (name "MANUFACTURER") "National Semiconductor")
        (field (name "DIGIKEYPARTNUMBER") "LMC6064IN-ND")
        (field (name "PUBLISHER") "Altium Limited")
      )
      (libsource (lib "NSC Amplifier") (part "LMC6064IN"))
    )
    (comp (ref "U4")
      (value "LMC6064IN")
      (footprint "N14A")
      (description "Precision CMOS Quad Micropower Operational Amplifier")
      (fields
        (field (name "MANUFACTURER") "National Semiconductor")
        (field (name "DIGIKEYPARTNUMBER") "LMC6064IN-ND")
        (field (name "PUBLISHER") "Altium Limited")
      )
      (libsource (lib "NSC Amplifier") (part "LMC6064IN"))
    )
    (comp (ref "U5") (value "ULN2003") (footprint "DIP16") (libsource (lib "Schlib1") (part "ULN2003")))
    (comp (ref "U6") (value "ULN2003") (footprint "DIP16") (libsource (lib "Schlib1") (part "ULN2003")))
    (comp (ref "U7") (value "ULN2003") (footprint "DIP16") (libsource (lib "Schlib1") (part "ULN2003")))
    (comp (ref "U7A") (value "ULN2003") (footprint "DIP16") (libsource (lib "Schlib1") (part "ULN2003")))
    (comp (ref "U8") (value "7805") (footprint "78xx") (libsource (lib "Schlib1") (part "7805")))
    (comp (ref "U10") (value "ICL7660") (footprint "DIP8") (libsource (lib "Schlib1") (part "ICL7660")))
  )
  (nets
    (net (code "1") (name "+5V") (class "Default")
      (node (ref "C1") (pin "2") (pinfunction "2_2") (pintype "passive"))
      (node (ref "C2") (pin "1") (pinfunction "1_1") (pintype "passive"))
      (node (ref "K1") (pin "3") (pinfunction "3_3") (pintype "passive"))
      (node (ref "K10") (pin "3") (pinfunction "3_3") (pintype "passive"))
      (node (ref "K11") (pin "3") (pinfunction "3_3") (pintype "passive"))
      (node (ref "K12") (pin "3") (pinfunction "3_3") (pintype "passive"))
      (node (ref "K13") (pin "3") (pinfunction "3_3") (pintype "passive"))
      (node (ref "K14") (pin "3") (pinfunction "3_3") (pintype "passive"))
      (node (ref "K15") (pin "3") (pinfunction "3_3") (pintype "passive"))
      (node (ref "K16") (pin "3") (pinfunction "3_3") (pintype "passive"))
      (node (ref "K17") (pin "3") (pinfunction "3_3") (pintype "passive"))
      (node (ref "K18") (pin "3") (pinfunction "3_3") (pintype "passive"))
      (node (ref "K2") (pin "3") (pinfunction "3_3") (pintype "passive"))
      (node (ref "K3") (pin "3") (pinfunction "3_3") (pintype "passive"))
      (node (ref "K4") (pin "3") (pinfunction "3_3") (pintype "passive"))
      (node (ref "K5") (pin "3") (pinfunction "3_3") (pintype "passive"))
      (node (ref "K6") (pin "3") (pinfunction "3_3") (pintype "passive"))
      (node (ref "K7") (pin "3") (pinfunction "3_3") (pintype "passive"))
      (node (ref "K8") (pin "3") (pinfunction "3_3") (pintype "passive"))
      (node (ref "K9") (pin "3") (pinfunction "3_3") (pintype "passive"))
      (node (ref "KG1") (pin "5") (pinfunction "T2_5") (pintype "passive"))
      (node (ref "KG2") (pin "5") (pinfunction "T2_5") (pintype "passive"))
      (node (ref "KG3") (pin "5") (pinfunction "T2_5") (pintype "passive"))
      (node (ref "KG4") (pin "5") (pinfunction "T2_5") (pintype "passive"))
      (node (ref "R3") (pin "2") (pinfunction "2_2") (pintype "passive"))
      (node (ref "R4") (pin "2") (pinfunction "2_2") (pintype "passive"))
      (node (ref "R43") (pin "2") (pinfunction "2_2") (pintype "passive"))
      (node (ref "R46") (pin "2") (pinfunction "2_2") (pintype "passive"))
      (node (ref "U1") (pin "4") (pinfunction "V+_4") (pintype "power_in"))
      (node (ref "U10") (pin "8") (pinfunction "V+_8") (pintype "passive"))
      (node (ref "U2") (pin "4") (pinfunction "V+_4") (pintype "power_in"))
      (node (ref "U3") (pin "4") (pinfunction "V+_4") (pintype "power_in"))
      (node (ref "U4") (pin "4") (pinfunction "V+_4") (pintype "power_in"))
      (node (ref "U5") (pin "9") (pinfunction "VCC_9") (pintype "passive"))
      (node (ref "U6") (pin "9") (pinfunction "VCC_9") (pintype "passive"))
      (node (ref "U7") (pin "9") (pinfunction "VCC_9") (pintype "passive"))
      (node (ref "U7A") (pin "9") (pinfunction "VCC_9") (pintype "passive"))
      (node (ref "U8") (pin "3") (pinfunction "Vout_3") (pintype "passive"))
    )
    (net (code "2") (name "-5V") (class "Default")
      (node (ref "C6") (pin "2") (pinfunction "2_2") (pintype "passive"))
      (node (ref "U1") (pin "11") (pinfunction "V-_11") (pintype "power_in"))
      (node (ref "U10") (pin "5") (pinfunction "VOUT_5") (pintype "passive"))
      (node (ref "U2") (pin "11") (pinfunction "V-_11") (pintype "power_in"))
      (node (ref "U3") (pin "11") (pinfunction "V-_11") (pintype "power_in"))
      (node (ref "U4") (pin "11") (pinfunction "V-_11") (pintype "power_in"))
    )
    (net (code "3") (name "/+9V") (class "Default")
      (node (ref "C7") (pin "1") (pinfunction "1_1") (pintype "passive"))
      (node (ref "P9") (pin "1") (pinfunction "1_1") (pintype "passive"))
      (node (ref "U8") (pin "1") (pinfunction "Vin_1") (pintype "passive"))
    )
    (net (code "4") (name "/I1_0.6A") (class "Default")
      (node (ref "K17") (pin "4") (pinfunction "4_4") (pintype "passive"))
      (node (ref "U6") (pin "16") (pinfunction "OUT_1_16") (pintype "passive"))
    )
    (net (code "5") (name "/I1_3A") (class "Default")
      (node (ref "P6") (pin "1") (pinfunction "1_1") (pintype "passive"))
      (node (ref "R79") (pin "1") (pinfunction "1_1") (pintype "passive"))
      (node (ref "R80") (pin "1") (pinfunction "1_1") (pintype "passive"))
      (node (ref "R86") (pin "2") (pinfunction "2_2") (pintype "passive"))
    )
    (net (code "6") (name "/I1_5mA") (class "Default")
      (node (ref "K13") (pin "4") (pinfunction "4_4") (pintype "passive"))
      (node (ref "U6") (pin "12") (pinfunction "OUT_5_12") (pintype "passive"))
    )
    (net (code "7") (name "/I1_50mA") (class "Default")
      (node (ref "K15") (pin "4") (pinfunction "4_4") (pintype "passive"))
      (node (ref "U6") (pin "15") (pinfunction "OUT_2_15") (pintype "passive"))
    )
    (net (code "8") (name "/I1_50uA") (class "Default")
      (node (ref "K9") (pin "4") (pinfunction "4_4") (pintype "passive"))
      (node (ref "U6") (pin "14") (pinfunction "OUT_3_14") (pintype "passive"))
    )
    (net (code "9") (name "/I1_300uA") (class "Default")
      (node (ref "K11") (pin "4") (pinfunction "4_4") (pintype "passive"))
      (node (ref "U6") (pin "13") (pinfunction "OUT_4_13") (pintype "passive"))
    )
    (net (code "10") (name "/I1_AD") (class "Default")
      (node (ref "D3") (pin "1") (pinfunction "K_1") (pintype "passive"))
      (node (ref "P5") (pin "10") (pinfunction "10_10") (pintype "passive"))
      (node (ref "R95") (pin "1") (pinfunction "1_1") (pintype "passive"))
    )
    (net (code "11") (name "/I2_0.6A") (class "Default")
      (node (ref "K18") (pin "4") (pinfunction "4_4") (pintype "passive"))
      (node (ref "U7") (pin "12") (pinfunction "OUT_5_12") (pintype "passive"))
    )
    (net (code "12") (name "/I2_3A") (class "Default")
      (node (ref "P7") (pin "1") (pinfunction "1_1") (pintype "passive"))
      (node (ref "R81") (pin "1") (pinfunction "1_1") (pintype "passive"))
      (node (ref "R82") (pin "1") (pinfunction "1_1") (pintype "passive"))
      (node (ref "R88") (pin "2") (pinfunction "2_2") (pintype "passive"))
    )
    (net (code "13") (name "/I2_5mA") (class "Default")
      (node (ref "K14") (pin "4") (pinfunction "4_4") (pintype "passive"))
      (node (ref "U7") (pin "14") (pinfunction "OUT_3_14") (pintype "passive"))
    )
    (net (code "14") (name "/I2_50mA") (class "Default")
      (node (ref "K16") (pin "4") (pinfunction "4_4") (pintype "passive"))
      (node (ref "U7") (pin "13") (pinfunction "OUT_4_13") (pintype "passive"))
    )
    (net (code "15") (name "/I2_50uA") (class "Default")
      (node (ref "K10") (pin "4") (pinfunction "4_4") (pintype "passive"))
      (node (ref "U7") (pin "16") (pinfunction "OUT_1_16") (pintype "passive"))
    )
    (net (code "16") (name "/I2_300uA") (class "Default")
      (node (ref "K12") (pin "4") (pinfunction "4_4") (pintype "passive"))
      (node (ref "U7") (pin "15") (pinfunction "OUT_2_15") (pintype "passive"))
    )
    (net (code "17") (name "/I2_AD") (class "Default")
      (node (ref "D4") (pin "1") (pinfunction "K_1") (pintype "passive"))
      (node (ref "P5") (pin "9") (pinfunction "9_9") (pintype "passive"))
      (node (ref "R96") (pin "1") (pinfunction "1_1") (pintype "passive"))
    )
    (net (code "18") (name "/IO_0") (class "Default")
      (node (ref "P5") (pin "1") (pinfunction "1_1") (pintype "passive"))
      (node (ref "U5") (pin "7") (pinfunction "IN_7_7") (pintype "passive"))
    )
    (net (code "19") (name "/IO_1") (class "Default")
      (node (ref "P5") (pin "2") (pinfunction "2_2") (pintype "passive"))
      (node (ref "U5") (pin "6") (pinfunction "IN_6_6") (pintype "passive"))
    )
    (net (code "20") (name "/IO_2") (class "Default")
      (node (ref "P5") (pin "3") (pinfunction "3_3") (pintype "passive"))
      (node (ref "U5") (pin "5") (pinfunction "IN_5_5") (pintype "passive"))
    )
    (net (code "21") (name "/IO_3") (class "Default")
      (node (ref "P5") (pin "4") (pinfunction "4_4") (pintype "passive"))
      (node (ref "U5") (pin "4") (pinfunction "IN_4_4") (pintype "passive"))
    )
    (net (code "22") (name "/IO_4") (class "Default")
      (node (ref "P5") (pin "5") (pinfunction "5_5") (pintype "passive"))
      (node (ref "U5") (pin "3") (pinfunction "IN_3_3") (pintype "passive"))
    )
    (net (code "23") (name "/IO_5") (class "Default")
      (node (ref "P5") (pin "6") (pinfunction "6_6") (pintype "passive"))
      (node (ref "U5") (pin "2") (pinfunction "IN_2_2") (pintype "passive"))
    )
    (net (code "24") (name "/IO_6") (class "Default")
      (node (ref "P5") (pin "7") (pinfunction "7_7") (pintype "passive"))
      (node (ref "U5") (pin "1") (pinfunction "IN_1_1") (pintype "passive"))
    )
    (net (code "25") (name "/IO_7") (class "Default")
      (node (ref "P5") (pin "8") (pinfunction "8_8") (pintype "passive"))
      (node (ref "U6") (pin "7") (pinfunction "IN_7_7") (pintype "passive"))
    )
    (net (code "26") (name "/IO_8") (class "Default")
      (node (ref "P5") (pin "11") (pinfunction "11_11") (pintype "passive"))
      (node (ref "U6") (pin "5") (pinfunction "IN_5_5") (pintype "passive"))
    )
    (net (code "27") (name "/IO_9") (class "Default")
      (node (ref "P5") (pin "12") (pinfunction "12_12") (pintype "passive"))
      (node (ref "U6") (pin "4") (pinfunction "IN_4_4") (pintype "passive"))
    )
    (net (code "28") (name "/IO_10") (class "Default")
      (node (ref "P5") (pin "13") (pinfunction "13_13") (pintype "passive"))
      (node (ref "U6") (pin "3") (pinfunction "IN_3_3") (pintype "passive"))
    )
    (net (code "29") (name "/IO_11") (class "Default")
      (node (ref "P5") (pin "14") (pinfunction "14_14") (pintype "passive"))
      (node (ref "U6") (pin "2") (pinfunction "IN_2_2") (pintype "passive"))
    )
    (net (code "30") (name "/IO_12") (class "Default")
      (node (ref "P5") (pin "15") (pinfunction "15_15") (pintype "passive"))
      (node (ref "U6") (pin "1") (pinfunction "IN_1_1") (pintype "passive"))
    )
    (net (code "31") (name "/IO_13") (class "Default")
      (node (ref "P5") (pin "16") (pinfunction "16_16") (pintype "passive"))
      (node (ref "U7") (pin "5") (pinfunction "IN_5_5") (pintype "passive"))
    )
    (net (code "32") (name "/IO_14") (class "Default")
      (node (ref "P5") (pin "17") (pinfunction "17_17") (pintype "passive"))
      (node (ref "U7") (pin "4") (pinfunction "IN_4_4") (pintype "passive"))
    )
    (net (code "33") (name "/IO_15") (class "Default")
      (node (ref "P5") (pin "18") (pinfunction "18_18") (pintype "passive"))
      (node (ref "U7") (pin "3") (pinfunction "IN_3_3") (pintype "passive"))
    )
    (net (code "34") (name "/IO_16") (class "Default")
      (node (ref "P5") (pin "19") (pinfunction "19_19") (pintype "passive"))
      (node (ref "U7") (pin "2") (pinfunction "IN_2_2") (pintype "passive"))
    )
    (net (code "35") (name "/IO_17") (class "Default")
      (node (ref "P5") (pin "20") (pinfunction "20_20") (pintype "passive"))
      (node (ref "U7") (pin "1") (pinfunction "IN_1_1") (pintype "passive"))
    )
    (net (code "36") (name "/IO_18") (class "Default")
      (node (ref "P5") (pin "23") (pinfunction "23_23") (pintype "passive"))
      (node (ref "U7A") (pin "4") (pinfunction "IN_4_4") (pintype "passive"))
    )
    (net (code "37") (name "/IO_19") (class "Default")
      (node (ref "P5") (pin "24") (pinfunction "24_24") (pintype "passive"))
      (node (ref "U7A") (pin "3") (pinfunction "IN_3_3") (pintype "passive"))
    )
    (net (code "38") (name "/IO_20") (class "Default")
      (node (ref "P5") (pin "25") (pinfunction "25_25") (pintype "passive"))
      (node (ref "U7A") (pin "2") (pinfunction "IN_2_2") (pintype "passive"))
    )
    (net (code "39") (name "/IO_21") (class "Default")
      (node (ref "P5") (pin "26") (pinfunction "26_26") (pintype "passive"))
      (node (ref "U7A") (pin "1") (pinfunction "IN_1_1") (pintype "passive"))
    )
    (net (code "40") (name "/KG1") (class "Default")
      (node (ref "KG1") (pin "4") (pinfunction "T1_4") (pintype "passive"))
      (node (ref "U7A") (pin "13") (pinfunction "OUT_4_13") (pintype "passive"))
    )
    (net (code "41") (name "/KG2") (class "Default")
      (node (ref "KG2") (pin "4") (pinfunction "T1_4") (pintype "passive"))
      (node (ref "U7A") (pin "14") (pinfunction "OUT_3_14") (pintype "passive"))
    )
    (net (code "42") (name "/KG3") (class "Default")
      (node (ref "KG3") (pin "4") (pinfunction "T1_4") (pintype "passive"))
      (node (ref "U7A") (pin "15") (pinfunction "OUT_2_15") (pintype "passive"))
    )
    (net (code "43") (name "/KG4") (class "Default")
      (node (ref "KG4") (pin "4") (pinfunction "T1_4") (pintype "passive"))
      (node (ref "U7A") (pin "16") (pinfunction "OUT_1_16") (pintype "passive"))
    )
    (net (code "44") (name "/U1_3V") (class "Default")
      (node (ref "K4") (pin "4") (pinfunction "4_4") (pintype "passive"))
      (node (ref "U5") (pin "11") (pinfunction "OUT_6_11") (pintype "passive"))
    )
    (net (code "45") (name "/U1_15V") (class "Default")
      (node (ref "K6") (pin "4") (pinfunction "4_4") (pintype "passive"))
      (node (ref "U5") (pin "12") (pinfunction "OUT_5_12") (pintype "passive"))
    )
    (net (code "46") (name "/U1_200V") (class "Default")
      (node (ref "K8") (pin "4") (pinfunction "4_4") (pintype "passive"))
      (node (ref "U5") (pin "13") (pinfunction "OUT_4_13") (pintype "passive"))
    )
    (net (code "47") (name "/U1_200mV") (class "Default")
      (node (ref "K2") (pin "4") (pinfunction "4_4") (pintype "passive"))
      (node (ref "U5") (pin "10") (pinfunction "OUT_7_10") (pintype "passive"))
    )
    (net (code "48") (name "/U1_AD") (class "Default")
      (node (ref "D1") (pin "1") (pinfunction "K_1") (pintype "passive"))
      (node (ref "P5") (pin "22") (pinfunction "22_22") (pintype "passive"))
      (node (ref "R92") (pin "1") (pinfunction "1_1") (pintype "passive"))
    )
    (net (code "49") (name "/U2_3V") (class "Default")
      (node (ref "K3") (pin "4") (pinfunction "4_4") (pintype "passive"))
      (node (ref "U5") (pin "15") (pinfunction "OUT_2_15") (pintype "passive"))
    )
    (net (code "50") (name "/U2_15V") (class "Default")
      (node (ref "K5") (pin "4") (pinfunction "4_4") (pintype "passive"))
      (node (ref "U5") (pin "16") (pinfunction "OUT_1_16") (pintype "passive"))
    )
    (net (code "51") (name "/U2_200V") (class "Default")
      (node (ref "K7") (pin "4") (pinfunction "4_4") (pintype "passive"))
      (node (ref "U6") (pin "10") (pinfunction "OUT_7_10") (pintype "passive"))
    )
    (net (code "52") (name "/U2_200mV") (class "Default")
      (node (ref "K1") (pin "4") (pinfunction "4_4") (pintype "passive"))
      (node (ref "U5") (pin "14") (pinfunction "OUT_3_14") (pintype "passive"))
    )
    (net (code "53") (name "/U2_AD") (class "Default")
      (node (ref "D2") (pin "1") (pinfunction "K_1") (pintype "passive"))
      (node (ref "P5") (pin "21") (pinfunction "21_21") (pintype "passive"))
      (node (ref "R91") (pin "1") (pinfunction "1_1") (pintype "passive"))
    )
    (net (code "54") (name "GND") (class "Default")
      (node (ref "C1") (pin "1") (pinfunction "1_1") (pintype "passive"))
      (node (ref "C2") (pin "2") (pinfunction "2_2") (pintype "passive"))
      (node (ref "C6") (pin "1") (pinfunction "1_1") (pintype "passive"))
      (node (ref "C7") (pin "2") (pinfunction "2_2") (pintype "passive"))
      (node (ref "D1") (pin "3") (pinfunction "A_3") (pintype "passive"))
      (node (ref "D2") (pin "3") (pinfunction "A_3") (pintype "passive"))
      (node (ref "D3") (pin "3") (pinfunction "A_3") (pintype "passive"))
      (node (ref "D4") (pin "3") (pinfunction "A_3") (pintype "passive"))
      (node (ref "KG1") (pin "1") (pinfunction "COM_1") (pintype "passive"))
      (node (ref "KG2") (pin "1") (pinfunction "COM_1") (pintype "passive"))
      (node (ref "KG3") (pin "1") (pinfunction "COM_1") (pintype "passive"))
      (node (ref "KG4") (pin "1") (pinfunction "COM_1") (pintype "passive"))
      (node (ref "P5") (pin "33") (pinfunction "33_33") (pintype "passive"))
      (node (ref "P9") (pin "2") (pinfunction "2_2") (pintype "passive"))
      (node (ref "R14") (pin "1") (pinfunction "1_1") (pintype "passive"))
      (node (ref "R16") (pin "1") (pinfunction "1_1") (pintype "passive"))
      (node (ref "R53") (pin "1") (pinfunction "1_1") (pintype "passive"))
      (node (ref "R54") (pin "1") (pinfunction "1_1") (pintype "passive"))
      (node (ref "R89") (pin "1") (pinfunction "1_1") (pintype "passive"))
      (node (ref "R90") (pin "1") (pinfunction "1_1") (pintype "passive"))
      (node (ref "R93") (pin "1") (pinfunction "1_1") (pintype "passive"))
      (node (ref "R94") (pin "1") (pinfunction "1_1") (pintype "passive"))
      (node (ref "U10") (pin "3") (pinfunction "GND_3") (pintype "passive"))
      (node (ref "U5") (pin "8") (pinfunction "GND_8") (pintype "passive"))
      (node (ref "U6") (pin "8") (pinfunction "GND_8") (pintype "passive"))
      (node (ref "U7") (pin "8") (pinfunction "GND_8") (pintype "passive"))
      (node (ref "U7A") (pin "8") (pinfunction "GND_8") (pintype "passive"))
      (node (ref "U8") (pin "2") (pinfunction "GND_2") (pintype "passive"))
    )
    (net (code "55") (name "Net-(F1-Pad1)") (class "Default")
      (node (ref "F1") (pin "1") (pinfunction "1_1") (pintype "passive"))
      (node (ref "P3") (pin "1") (pinfunction "1_1") (pintype "passive"))
    )
    (net (code "56") (name "Net-(F1-Pad2)") (class "Default")
      (node (ref "F1") (pin "2") (pinfunction "2_2") (pintype "passive"))
      (node (ref "K11") (pin "1") (pinfunction "1_1") (pintype "passive"))
      (node (ref "K13") (pin "1") (pinfunction "1_1") (pintype "passive"))
      (node (ref "K15") (pin "1") (pinfunction "1_1") (pintype "passive"))
      (node (ref "K17") (pin "1") (pinfunction "1_1") (pintype "passive"))
      (node (ref "K9") (pin "1") (pinfunction "1_1") (pintype "passive"))
    )
    (net (code "57") (name "Net-(F2-Pad1)") (class "Default")
      (node (ref "F2") (pin "1") (pinfunction "1_1") (pintype "passive"))
      (node (ref "P4") (pin "1") (pinfunction "1_1") (pintype "passive"))
    )
    (net (code "58") (name "Net-(F2-Pad2)") (class "Default")
      (node (ref "F2") (pin "2") (pinfunction "2_2") (pintype "passive"))
      (node (ref "K10") (pin "1") (pinfunction "1_1") (pintype "passive"))
      (node (ref "K12") (pin "1") (pinfunction "1_1") (pintype "passive"))
      (node (ref "K14") (pin "1") (pinfunction "1_1") (pintype "passive"))
      (node (ref "K16") (pin "1") (pinfunction "1_1") (pintype "passive"))
      (node (ref "K18") (pin "1") (pinfunction "1_1") (pintype "passive"))
    )
    (net (code "59") (name "Net-(K1-Pad1)") (class "Default")
      (node (ref "K1") (pin "1") (pinfunction "1_1") (pintype "passive"))
      (node (ref "P1") (pin "1") (pinfunction "1_1") (pintype "passive"))
      (node (ref "R1") (pin "2") (pinfunction "2_2") (pintype "passive"))
      (node (ref "R6") (pin "2") (pinfunction "2_2") (pintype "passive"))
    )
    (net (code "60") (name "Net-(K2-Pad1)") (class "Default")
      (node (ref "K2") (pin "1") (pinfunction "1_1") (pintype "passive"))
      (node (ref "P2") (pin "1") (pinfunction "1_1") (pintype "passive"))
      (node (ref "R2") (pin "2") (pinfunction "2_2") (pintype "passive"))
      (node (ref "R9") (pin "2") (pinfunction "2_2") (pintype "passive"))
    )
    (net (code "61") (name "Net-(K3-Pad1)") (class "Default")
      (node (ref "K3") (pin "1") (pinfunction "1_1") (pintype "passive"))
      (node (ref "R12") (pin "2") (pinfunction "2_2") (pintype "passive"))
      (node (ref "R20") (pin "2") (pinfunction "2_2") (pintype "passive"))
      (node (ref "R5") (pin "1") (pinfunction "1_1") (pintype "passive"))
      (node (ref "R6") (pin "1") (pinfunction "1_1") (pintype "passive"))
    )
    (net (code "62") (name "Net-(K4-Pad1)") (class "Default")
      (node (ref "K4") (pin "1") (pinfunction "1_1") (pintype "passive"))
      (node (ref "R15") (pin "2") (pinfunction "2_2") (pintype "passive"))
      (node (ref "R24") (pin "2") (pinfunction "2_2") (pintype "passive"))
      (node (ref "R8") (pin "1") (pinfunction "1_1") (pintype "passive"))
      (node (ref "R9") (pin "1") (pinfunction "1_1") (pintype "passive"))
    )
    (net (code "63") (name "Net-(K5-Pad1)") (class "Default")
      (node (ref "K5") (pin "1") (pinfunction "1_1") (pintype "passive"))
      (node (ref "R19") (pin "1") (pinfunction "1_1") (pintype "passive"))
      (node (ref "R20") (pin "1") (pinfunction "1_1") (pintype "passive"))
      (node (ref "R25") (pin "2") (pinfunction "2_2") (pintype "passive"))
      (node (ref "R28") (pin "2") (pinfunction "2_2") (pintype "passive"))
    )
    (net (code "64") (name "Net-(K6-Pad1)") (class "Default")
      (node (ref "K6") (pin "1") (pinfunction "1_1") (pintype "passive"))
      (node (ref "R23") (pin "1") (pinfunction "1_1") (pintype "passive"))
      (node (ref "R24") (pin "1") (pinfunction "1_1") (pintype "passive"))
      (node (ref "R26") (pin "2") (pinfunction "2_2") (pintype "passive"))
      (node (ref "R31") (pin "2") (pinfunction "2_2") (pintype "passive"))
    )
    (net (code "65") (name "Net-(K7-Pad1)") (class "Default")
      (node (ref "K7") (pin "1") (pinfunction "1_1") (pintype "passive"))
      (node (ref "R27") (pin "1") (pinfunction "1_1") (pintype "passive"))
      (node (ref "R28") (pin "1") (pinfunction "1_1") (pintype "passive"))
      (node (ref "R33") (pin "2") (pinfunction "2_2") (pintype "passive"))
      (node (ref "R36") (pin "2") (pinfunction "2_2") (pintype "passive"))
    )
    (net (code "66") (name "Net-(K8-Pad1)") (class "Default")
      (node (ref "K8") (pin "1") (pinfunction "1_1") (pintype "passive"))
      (node (ref "R30") (pin "1") (pinfunction "1_1") (pintype "passive"))
      (node (ref "R31") (pin "1") (pinfunction "1_1") (pintype "passive"))
      (node (ref "R34") (pin "2") (pinfunction "2_2") (pintype "passive"))
      (node (ref "R38") (pin "2") (pinfunction "2_2") (pintype "passive"))
    )
    (net (code "67") (name "Net-(K11-Pad2)") (class "Default")
      (node (ref "K11") (pin "2") (pinfunction "2_2") (pintype "passive"))
      (node (ref "R41") (pin "1") (pinfunction "1_1") (pintype "passive"))
      (node (ref "R42") (pin "1") (pinfunction "1_1") (pintype "passive"))
      (node (ref "R49") (pin "2") (pinfunction "2_2") (pintype "passive"))
      (node (ref "R56") (pin "2") (pinfunction "2_2") (pintype "passive"))
    )
    (net (code "68") (name "Net-(K12-Pad2)") (class "Default")
      (node (ref "K12") (pin "2") (pinfunction "2_2") (pintype "passive"))
      (node (ref "R44") (pin "1") (pinfunction "1_1") (pintype "passive"))
      (node (ref "R45") (pin "1") (pinfunction "1_1") (pintype "passive"))
      (node (ref "R50") (pin "2") (pinfunction "2_2") (pintype "passive"))
      (node (ref "R58") (pin "2") (pinfunction "2_2") (pintype "passive"))
    )
    (net (code "69") (name "Net-(K13-Pad2)") (class "Default")
      (node (ref "K13") (pin "2") (pinfunction "2_2") (pintype "passive"))
      (node (ref "R55") (pin "1") (pinfunction "1_1") (pintype "passive"))
      (node (ref "R56") (pin "1") (pinfunction "1_1") (pintype "passive"))
      (node (ref "R63") (pin "2") (pinfunction "2_2") (pintype "passive"))
      (node (ref "R66") (pin "2") (pinfunction "2_2") (pintype "passive"))
    )
    (net (code "70") (name "Net-(K14-Pad2)") (class "Default")
      (node (ref "K14") (pin "2") (pinfunction "2_2") (pintype "passive"))
      (node (ref "R57") (pin "1") (pinfunction "1_1") (pintype "passive"))
      (node (ref "R58") (pin "1") (pinfunction "1_1") (pintype "passive"))
      (node (ref "R64") (pin "2") (pinfunction "2_2") (pintype "passive"))
      (node (ref "R68") (pin "2") (pinfunction "2_2") (pintype "passive"))
    )
    (net (code "71") (name "Net-(K15-Pad2)") (class "Default")
      (node (ref "K15") (pin "2") (pinfunction "2_2") (pintype "passive"))
      (node (ref "R65") (pin "1") (pinfunction "1_1") (pintype "passive"))
      (node (ref "R66") (pin "1") (pinfunction "1_1") (pintype "passive"))
      (node (ref "R71") (pin "2") (pinfunction "2_2") (pintype "passive"))
      (node (ref "R74") (pin "2") (pinfunction "2_2") (pintype "passive"))
    )
    (net (code "72") (name "Net-(K16-Pad2)") (class "Default")
      (node (ref "K16") (pin "2") (pinfunction "2_2") (pintype "passive"))
      (node (ref "R67") (pin "1") (pinfunction "1_1") (pintype "passive"))
      (node (ref "R68") (pin "1") (pinfunction "1_1") (pintype "passive"))
      (node (ref "R72") (pin "2") (pinfunction "2_2") (pintype "passive"))
      (node (ref "R76") (pin "2") (pinfunction "2_2") (pintype "passive"))
    )
    (net (code "73") (name "Net-(K17-Pad2)") (class "Default")
      (node (ref "K17") (pin "2") (pinfunction "2_2") (pintype "passive"))
      (node (ref "R73") (pin "1") (pinfunction "1_1") (pintype "passive"))
      (node (ref "R74") (pin "1") (pinfunction "1_1") (pintype "passive"))
      (node (ref "R77") (pin "2") (pinfunction "2_2") (pintype "passive"))
      (node (ref "R80") (pin "2") (pinfunction "2_2") (pintype "passive"))
    )
    (net (code "74") (name "Net-(K18-Pad2)") (class "Default")
      (node (ref "K18") (pin "2") (pinfunction "2_2") (pintype "passive"))
      (node (ref "R75") (pin "1") (pinfunction "1_1") (pintype "passive"))
      (node (ref "R76") (pin "1") (pinfunction "1_1") (pintype "passive"))
      (node (ref "R78") (pin "2") (pinfunction "2_2") (pintype "passive"))
      (node (ref "R82") (pin "2") (pinfunction "2_2") (pintype "passive"))
    )
    (net (code "75") (name "Net-(KG1-NC)") (class "Default")
      (node (ref "K2") (pin "2") (pinfunction "2_2") (pintype "passive"))
      (node (ref "K4") (pin "2") (pinfunction "2_2") (pintype "passive"))
      (node (ref "K6") (pin "2") (pinfunction "2_2") (pintype "passive"))
      (node (ref "K8") (pin "2") (pinfunction "2_2") (pintype "passive"))
      (node (ref "KG1") (pin "2") (pinfunction "NC_2") (pintype "passive"))
      (node (ref "U1") (pin "10") (pinfunction "IN3+_10") (pintype "input"))
    )
    (net (code "76") (name "Net-(KG1-NO)") (class "Default")
      (node (ref "KG1") (pin "3") (pinfunction "NO_3") (pintype "passive"))
      (node (ref "P2") (pin "2") (pinfunction "2_2") (pintype "passive"))
      (node (ref "R37") (pin "1") (pinfunction "1_1") (pintype "passive"))
      (node (ref "R38") (pin "1") (pinfunction "1_1") (pintype "passive"))
    )
    (net (code "77") (name "Net-(KG2-NC)") (class "Default")
      (node (ref "K1") (pin "2") (pinfunction "2_2") (pintype "passive"))
      (node (ref "K3") (pin "2") (pinfunction "2_2") (pintype "passive"))
      (node (ref "K5") (pin "2") (pinfunction "2_2") (pintype "passive"))
      (node (ref "K7") (pin "2") (pinfunction "2_2") (pintype "passive"))
      (node (ref "KG2") (pin "2") (pinfunction "NC_2") (pintype "passive"))
      (node (ref "U2") (pin "10") (pinfunction "IN3+_10") (pintype "input"))
    )
    (net (code "78") (name "Net-(KG2-NO)") (class "Default")
      (node (ref "KG2") (pin "3") (pinfunction "NO_3") (pintype "passive"))
      (node (ref "P1") (pin "2") (pinfunction "2_2") (pintype "passive"))
      (node (ref "R35") (pin "1") (pinfunction "1_1") (pintype "passive"))
      (node (ref "R36") (pin "1") (pinfunction "1_1") (pintype "passive"))
    )
    (net (code "79") (name "Net-(KG3-NC)") (class "Default")
      (node (ref "K9") (pin "2") (pinfunction "2_2") (pintype "passive"))
      (node (ref "KG3") (pin "2") (pinfunction "NC_2") (pintype "passive"))
      (node (ref "R39") (pin "2") (pinfunction "2_2") (pintype "passive"))
      (node (ref "R42") (pin "2") (pinfunction "2_2") (pintype "passive"))
      (node (ref "U3") (pin "10") (pinfunction "IN3+_10") (pintype "input"))
    )
    (net (code "80") (name "Net-(KG3-NO)") (class "Default")
      (node (ref "KG3") (pin "3") (pinfunction "NO_3") (pintype "passive"))
      (node (ref "P3") (pin "2") (pinfunction "2_2") (pintype "passive"))
      (node (ref "P6") (pin "2") (pinfunction "2_2") (pintype "passive"))
      (node (ref "R86") (pin "1") (pinfunction "1_1") (pintype "passive"))
    )
    (net (code "81") (name "Net-(KG4-NC)") (class "Default")
      (node (ref "K10") (pin "2") (pinfunction "2_2") (pintype "passive"))
      (node (ref "KG4") (pin "2") (pinfunction "NC_2") (pintype "passive"))
      (node (ref "R40") (pin "2") (pinfunction "2_2") (pintype "passive"))
      (node (ref "R45") (pin "2") (pinfunction "2_2") (pintype "passive"))
      (node (ref "U4") (pin "10") (pinfunction "IN3+_10") (pintype "input"))
    )
    (net (code "82") (name "Net-(KG4-NO)") (class "Default")
      (node (ref "KG4") (pin "3") (pinfunction "NO_3") (pintype "passive"))
      (node (ref "P4") (pin "2") (pinfunction "2_2") (pintype "passive"))
      (node (ref "P7") (pin "2") (pinfunction "2_2") (pintype "passive"))
      (node (ref "R88") (pin "1") (pinfunction "1_1") (pintype "passive"))
    )
    (net (code "83") (name "Net-(R1-Pad1)") (class "Default")
      (node (ref "R1") (pin "1") (pinfunction "1_1") (pintype "passive"))
      (node (ref "R5") (pin "2") (pinfunction "2_2") (pintype "passive"))
    )
    (net (code "84") (name "Net-(R2-Pad1)") (class "Default")
      (node (ref "R2") (pin "1") (pinfunction "1_1") (pintype "passive"))
      (node (ref "R8") (pin "2") (pinfunction "2_2") (pintype "passive"))
    )
    (net (code "85") (name "Net-(R12-Pad1)") (class "Default")
      (node (ref "R12") (pin "1") (pinfunction "1_1") (pintype "passive"))
      (node (ref "R19") (pin "2") (pinfunction "2_2") (pintype "passive"))
    )
    (net (code "86") (name "Net-(R15-Pad1)") (class "Default")
      (node (ref "R15") (pin "1") (pinfunction "1_1") (pintype "passive"))
      (node (ref "R23") (pin "2") (pinfunction "2_2") (pintype "passive"))
    )
    (net (code "87") (name "Net-(R25-Pad1)") (class "Default")
      (node (ref "R25") (pin "1") (pinfunction "1_1") (pintype "passive"))
      (node (ref "R27") (pin "2") (pinfunction "2_2") (pintype "passive"))
    )
    (net (code "88") (name "Net-(R26-Pad1)") (class "Default")
      (node (ref "R26") (pin "1") (pinfunction "1_1") (pintype "passive"))
      (node (ref "R30") (pin "2") (pinfunction "2_2") (pintype "passive"))
    )
    (net (code "89") (name "Net-(R33-Pad1)") (class "Default")
      (node (ref "R33") (pin "1") (pinfunction "1_1") (pintype "passive"))
      (node (ref "R35") (pin "2") (pinfunction "2_2") (pintype "passive"))
    )
    (net (code "90") (name "Net-(R34-Pad1)") (class "Default")
      (node (ref "R34") (pin "1") (pinfunction "1_1") (pintype "passive"))
      (node (ref "R37") (pin "2") (pinfunction "2_2") (pintype "passive"))
    )
    (net (code "91") (name "Net-(R39-Pad1)") (class "Default")
      (node (ref "R39") (pin "1") (pinfunction "1_1") (pintype "passive"))
      (node (ref "R41") (pin "2") (pinfunction "2_2") (pintype "passive"))
    )
    (net (code "92") (name "Net-(R40-Pad1)") (class "Default")
      (node (ref "R40") (pin "1") (pinfunction "1_1") (pintype "passive"))
      (node (ref "R44") (pin "2") (pinfunction "2_2") (pintype "passive"))
    )
    (net (code "93") (name "Net-(R49-Pad1)") (class "Default")
      (node (ref "R49") (pin "1") (pinfunction "1_1") (pintype "passive"))
      (node (ref "R55") (pin "2") (pinfunction "2_2") (pintype "passive"))
    )
    (net (code "94") (name "Net-(R50-Pad1)") (class "Default")
      (node (ref "R50") (pin "1") (pinfunction "1_1") (pintype "passive"))
      (node (ref "R57") (pin "2") (pinfunction "2_2") (pintype "passive"))
    )
    (net (code "95") (name "Net-(R59-Pad2)") (class "Default")
      (node (ref "R59") (pin "2") (pinfunction "2_2") (pintype "passive"))
      (node (ref "R61") (pin "1") (pinfunction "1_1") (pintype "passive"))
    )
    (net (code "96") (name "Net-(R60-Pad2)") (class "Default")
      (node (ref "R60") (pin "2") (pinfunction "2_2") (pintype "passive"))
      (node (ref "R62") (pin "1") (pinfunction "1_1") (pintype "passive"))
    )
    (net (code "97") (name "Net-(R63-Pad1)") (class "Default")
      (node (ref "R63") (pin "1") (pinfunction "1_1") (pintype "passive"))
      (node (ref "R65") (pin "2") (pinfunction "2_2") (pintype "passive"))
    )
    (net (code "98") (name "Net-(R64-Pad1)") (class "Default")
      (node (ref "R64") (pin "1") (pinfunction "1_1") (pintype "passive"))
      (node (ref "R67") (pin "2") (pinfunction "2_2") (pintype "passive"))
    )
    (net (code "99") (name "Net-(R71-Pad1)") (class "Default")
      (node (ref "R71") (pin "1") (pinfunction "1_1") (pintype "passive"))
      (node (ref "R73") (pin "2") (pinfunction "2_2") (pintype "passive"))
    )
    (net (code "100") (name "Net-(R72-Pad1)") (class "Default")
      (node (ref "R72") (pin "1") (pinfunction "1_1") (pintype "passive"))
      (node (ref "R75") (pin "2") (pinfunction "2_2") (pintype "passive"))
    )
    (net (code "101") (name "Net-(R77-Pad1)") (class "Default")
      (node (ref "R77") (pin "1") (pinfunction "1_1") (pintype "passive"))
      (node (ref "R79") (pin "2") (pinfunction "2_2") (pintype "passive"))
    )
    (net (code "102") (name "Net-(R78-Pad1)") (class "Default")
      (node (ref "R78") (pin "1") (pinfunction "1_1") (pintype "passive"))
      (node (ref "R81") (pin "2") (pinfunction "2_2") (pintype "passive"))
    )
    (net (code "103") (name "Net-(U1A-IN1+)") (class "Default")
      (node (ref "R4") (pin "1") (pinfunction "1_1") (pintype "passive"))
      (node (ref "R90") (pin "2") (pinfunction "2_2") (pintype "passive"))
      (node (ref "U1") (pin "3") (pinfunction "IN1+_3") (pintype "input"))
    )
    (net (code "104") (name "Net-(U1A-IN1-)") (class "Default")
      (node (ref "R11") (pin "2") (pinfunction "2_2") (pintype "passive"))
      (node (ref "U1") (pin "1") (pinfunction "OUT1_1") (pintype "output"))
      (node (ref "U1") (pin "2") (pinfunction "IN1-_2") (pintype "input"))
    )
    (net (code "105") (name "Net-(U1B-IN2+)") (class "Default")
      (node (ref "R11") (pin "1") (pinfunction "1_1") (pintype "passive"))
      (node (ref "R32") (pin "1") (pinfunction "1_1") (pintype "passive"))
      (node (ref "U1") (pin "5") (pinfunction "IN2+_5") (pintype "input"))
    )
    (net (code "106") (name "Net-(U1B-IN2-)") (class "Default")
      (node (ref "R16") (pin "2") (pinfunction "2_2") (pintype "passive"))
      (node (ref "R21") (pin "1") (pinfunction "1_1") (pintype "passive"))
      (node (ref "U1") (pin "6") (pinfunction "IN2-_6") (pintype "input"))
    )
    (net (code "107") (name "Net-(U1B-OUT2)") (class "Default")
      (node (ref "R21") (pin "2") (pinfunction "2_2") (pintype "passive"))
      (node (ref "R92") (pin "2") (pinfunction "2_2") (pintype "passive"))
      (node (ref "U1") (pin "7") (pinfunction "OUT2_7") (pintype "output"))
    )
    (net (code "108") (name "Net-(U1C-IN3-)") (class "Default")
      (node (ref "R32") (pin "2") (pinfunction "2_2") (pintype "passive"))
      (node (ref "U1") (pin "8") (pinfunction "OUT3_8") (pintype "output"))
      (node (ref "U1") (pin "9") (pinfunction "IN3-_9") (pintype "input"))
    )
    (net (code "109") (name "Net-(U2A-IN1+)") (class "Default")
      (node (ref "R3") (pin "1") (pinfunction "1_1") (pintype "passive"))
      (node (ref "R89") (pin "2") (pinfunction "2_2") (pintype "passive"))
      (node (ref "U2") (pin "3") (pinfunction "IN1+_3") (pintype "input"))
    )
    (net (code "110") (name "Net-(U2A-IN1-)") (class "Default")
      (node (ref "R7") (pin "2") (pinfunction "2_2") (pintype "passive"))
      (node (ref "U2") (pin "1") (pinfunction "OUT1_1") (pintype "output"))
      (node (ref "U2") (pin "2") (pinfunction "IN1-_2") (pintype "input"))
    )
    (net (code "111") (name "Net-(U2B-IN2+)") (class "Default")
      (node (ref "R29") (pin "1") (pinfunction "1_1") (pintype "passive"))
      (node (ref "R7") (pin "1") (pinfunction "1_1") (pintype "passive"))
      (node (ref "U2") (pin "5") (pinfunction "IN2+_5") (pintype "input"))
    )
    (net (code "112") (name "Net-(U2B-IN2-)") (class "Default")
      (node (ref "R14") (pin "2") (pinfunction "2_2") (pintype "passive"))
      (node (ref "R17") (pin "1") (pinfunction "1_1") (pintype "passive"))
      (node (ref "U2") (pin "6") (pinfunction "IN2-_6") (pintype "input"))
    )
    (net (code "113") (name "Net-(U2B-OUT2)") (class "Default")
      (node (ref "R17") (pin "2") (pinfunction "2_2") (pintype "passive"))
      (node (ref "R91") (pin "2") (pinfunction "2_2") (pintype "passive"))
      (node (ref "U2") (pin "7") (pinfunction "OUT2_7") (pintype "output"))
    )
    (net (code "114") (name "Net-(U2C-IN3-)") (class "Default")
      (node (ref "R29") (pin "2") (pinfunction "2_2") (pintype "passive"))
      (node (ref "U2") (pin "8") (pinfunction "OUT3_8") (pintype "output"))
      (node (ref "U2") (pin "9") (pinfunction "IN3-_9") (pintype "input"))
    )
    (net (code "115") (name "Net-(U3A-IN1+)") (class "Default")
      (node (ref "R43") (pin "1") (pinfunction "1_1") (pintype "passive"))
      (node (ref "R93") (pin "2") (pinfunction "2_2") (pintype "passive"))
      (node (ref "U3") (pin "3") (pinfunction "IN1+_3") (pintype "input"))
    )
    (net (code "116") (name "Net-(U3A-IN1-)") (class "Default")
      (node (ref "R47") (pin "2") (pinfunction "2_2") (pintype "passive"))
      (node (ref "U3") (pin "1") (pinfunction "OUT1_1") (pintype "output"))
      (node (ref "U3") (pin "2") (pinfunction "IN1-_2") (pintype "input"))
    )
    (net (code "117") (name "Net-(U3B-IN2+)") (class "Default")
      (node (ref "R47") (pin "1") (pinfunction "1_1") (pintype "passive"))
      (node (ref "R69") (pin "1") (pinfunction "1_1") (pintype "passive"))
      (node (ref "U3") (pin "5") (pinfunction "IN2+_5") (pintype "input"))
    )
    (net (code "118") (name "Net-(U3B-IN2-)") (class "Default")
      (node (ref "R53") (pin "2") (pinfunction "2_2") (pintype "passive"))
      (node (ref "R59") (pin "1") (pinfunction "1_1") (pintype "passive"))
      (node (ref "U3") (pin "6") (pinfunction "IN2-_6") (pintype "input"))
    )
    (net (code "119") (name "Net-(U3B-OUT2)") (class "Default")
      (node (ref "R61") (pin "2") (pinfunction "2_2") (pintype "passive"))
      (node (ref "R95") (pin "2") (pinfunction "2_2") (pintype "passive"))
      (node (ref "U3") (pin "7") (pinfunction "OUT2_7") (pintype "output"))
    )
    (net (code "120") (name "Net-(U3C-IN3-)") (class "Default")
      (node (ref "R69") (pin "2") (pinfunction "2_2") (pintype "passive"))
      (node (ref "U3") (pin "8") (pinfunction "OUT3_8") (pintype "output"))
      (node (ref "U3") (pin "9") (pinfunction "IN3-_9") (pintype "input"))
    )
    (net (code "121") (name "Net-(U4A-IN1+)") (class "Default")
      (node (ref "R46") (pin "1") (pinfunction "1_1") (pintype "passive"))
      (node (ref "R94") (pin "2") (pinfunction "2_2") (pintype "passive"))
      (node (ref "U4") (pin "3") (pinfunction "IN1+_3") (pintype "input"))
    )
    (net (code "122") (name "Net-(U4A-IN1-)") (class "Default")
      (node (ref "R48") (pin "2") (pinfunction "2_2") (pintype "passive"))
      (node (ref "U4") (pin "1") (pinfunction "OUT1_1") (pintype "output"))
      (node (ref "U4") (pin "2") (pinfunction "IN1-_2") (pintype "input"))
    )
    (net (code "123") (name "Net-(U4B-IN2+)") (class "Default")
      (node (ref "R48") (pin "1") (pinfunction "1_1") (pintype "passive"))
      (node (ref "R70") (pin "1") (pinfunction "1_1") (pintype "passive"))
      (node (ref "U4") (pin "5") (pinfunction "IN2+_5") (pintype "input"))
    )
    (net (code "124") (name "Net-(U4B-IN2-)") (class "Default")
      (node (ref "R54") (pin "2") (pinfunction "2_2") (pintype "passive"))
      (node (ref "R60") (pin "1") (pinfunction "1_1") (pintype "passive"))
      (node (ref "U4") (pin "6") (pinfunction "IN2-_6") (pintype "input"))
    )
    (net (code "125") (name "Net-(U4B-OUT2)") (class "Default")
      (node (ref "R62") (pin "2") (pinfunction "2_2") (pintype "passive"))
      (node (ref "R96") (pin "2") (pinfunction "2_2") (pintype "passive"))
      (node (ref "U4") (pin "7") (pinfunction "OUT2_7") (pintype "output"))
    )
    (net (code "126") (name "Net-(U4C-IN3-)") (class "Default")
      (node (ref "R70") (pin "2") (pinfunction "2_2") (pintype "passive"))
      (node (ref "U4") (pin "8") (pinfunction "OUT3_8") (pintype "output"))
      (node (ref "U4") (pin "9") (pinfunction "IN3-_9") (pintype "input"))
    )
    (net (code "127") (name "Net-(U10-CAP+)") (class "Default")
      (node (ref "C5") (pin "1") (pinfunction "1_1") (pintype "passive"))
      (node (ref "U10") (pin "2") (pinfunction "CAP+_2") (pintype "passive"))
    )
    (net (code "128") (name "Net-(U10-CAP-)") (class "Default")
      (node (ref "C5") (pin "2") (pinfunction "2_2") (pintype "passive"))
      (node (ref "U10") (pin "4") (pinfunction "CAP-_4") (pintype "passive"))
    )
    (net (code "129") (name "unconnected-(P5-Pad27)") (class "Default")
      (node (ref "P5") (pin "27") (pinfunction "27_27") (pintype "passive"))
    )
    (net (code "130") (name "unconnected-(P5-Pad28)") (class "Default")
      (node (ref "P5") (pin "28") (pinfunction "28_28") (pintype "passive"))
    )
    (net (code "131") (name "unconnected-(P5-Pad29)") (class "Default")
      (node (ref "P5") (pin "29") (pinfunction "29_29") (pintype "passive"))
    )
    (net (code "132") (name "unconnected-(P5-Pad30)") (class "Default")
      (node (ref "P5") (pin "30") (pinfunction "30_30") (pintype "passive"))
    )
    (net (code "133") (name "unconnected-(P5-Pad31)") (class "Default")
      (node (ref "P5") (pin "31") (pinfunction "31_31") (pintype "passive"))
    )
    (net (code "134") (name "unconnected-(P5-Pad32)") (class "Default")
      (node (ref "P5") (pin "32") (pinfunction "32_32") (pintype "passive"))
    )
    (net (code "135") (name "unconnected-(P5-Pad34)") (class "Default")
      (node (ref "P5") (pin "34") (pinfunction "34_34") (pintype "passive"))
    )
    (net (code "136") (name "unconnected-(U6-IN_6-Pad6)") (class "Default")
      (node (ref "U6") (pin "6") (pinfunction "IN_6_6") (pintype "passive"))
    )
    (net (code "137") (name "unconnected-(U6-OUT_6-Pad11)") (class "Default")
      (node (ref "U6") (pin "11") (pinfunction "OUT_6_11") (pintype "passive"))
    )
    (net (code "138") (name "unconnected-(U7-IN_6-Pad6)") (class "Default")
      (node (ref "U7") (pin "6") (pinfunction "IN_6_6") (pintype "passive"))
    )
    (net (code "139") (name "unconnected-(U7-IN_7-Pad7)") (class "Default")
      (node (ref "U7") (pin "7") (pinfunction "IN_7_7") (pintype "passive"))
    )
    (net (code "140") (name "unconnected-(U7-OUT_6-Pad11)") (class "Default")
      (node (ref "U7") (pin "11") (pinfunction "OUT_6_11") (pintype "passive"))
    )
    (net (code "141") (name "unconnected-(U7-OUT_7-Pad10)") (class "Default")
      (node (ref "U7") (pin "10") (pinfunction "OUT_7_10") (pintype "passive"))
    )
    (net (code "142") (name "unconnected-(U7A-IN_5-Pad5)") (class "Default")
      (node (ref "U7A") (pin "5") (pinfunction "IN_5_5") (pintype "passive"))
    )
    (net (code "143") (name "unconnected-(U7A-IN_6-Pad6)") (class "Default")
      (node (ref "U7A") (pin "6") (pinfunction "IN_6_6") (pintype "passive"))
    )
    (net (code "144") (name "unconnected-(U7A-IN_7-Pad7)") (class "Default")
      (node (ref "U7A") (pin "7") (pinfunction "IN_7_7") (pintype "passive"))
    )
    (net (code "145") (name "unconnected-(U7A-OUT_5-Pad12)") (class "Default")
      (node (ref "U7A") (pin "12") (pinfunction "OUT_5_12") (pintype "passive"))
    )
    (net (code "146") (name "unconnected-(U7A-OUT_6-Pad11)") (class "Default")
      (node (ref "U7A") (pin "11") (pinfunction "OUT_6_11") (pintype "passive"))
    )
    (net (code "147") (name "unconnected-(U7A-OUT_7-Pad10)") (class "Default")
      (node (ref "U7A") (pin "10") (pinfunction "OUT_7_10") (pintype "passive"))
    )
    (net (code "148") (name "unconnected-(U10-LV-Pad6)") (class "Default")
      (node (ref "U10") (pin "6") (pinfunction "LV_6") (pintype "passive"))
    )
    (net (code "149") (name "unconnected-(U10-NC{slash}Boost-Pad1)") (class "Default")
      (node (ref "U10") (pin "1") (pinfunction "NC/Boost_1") (pintype "passive"))
    )
    (net (code "150") (name "unconnected-(U10-OSC-Pad7)") (class "Default")
      (node (ref "U10") (pin "7") (pinfunction "OSC_7") (pintype "passive"))
    )
  )
)
